# v8g.net
KiCad netlist of a schematic drawn in EAGLE
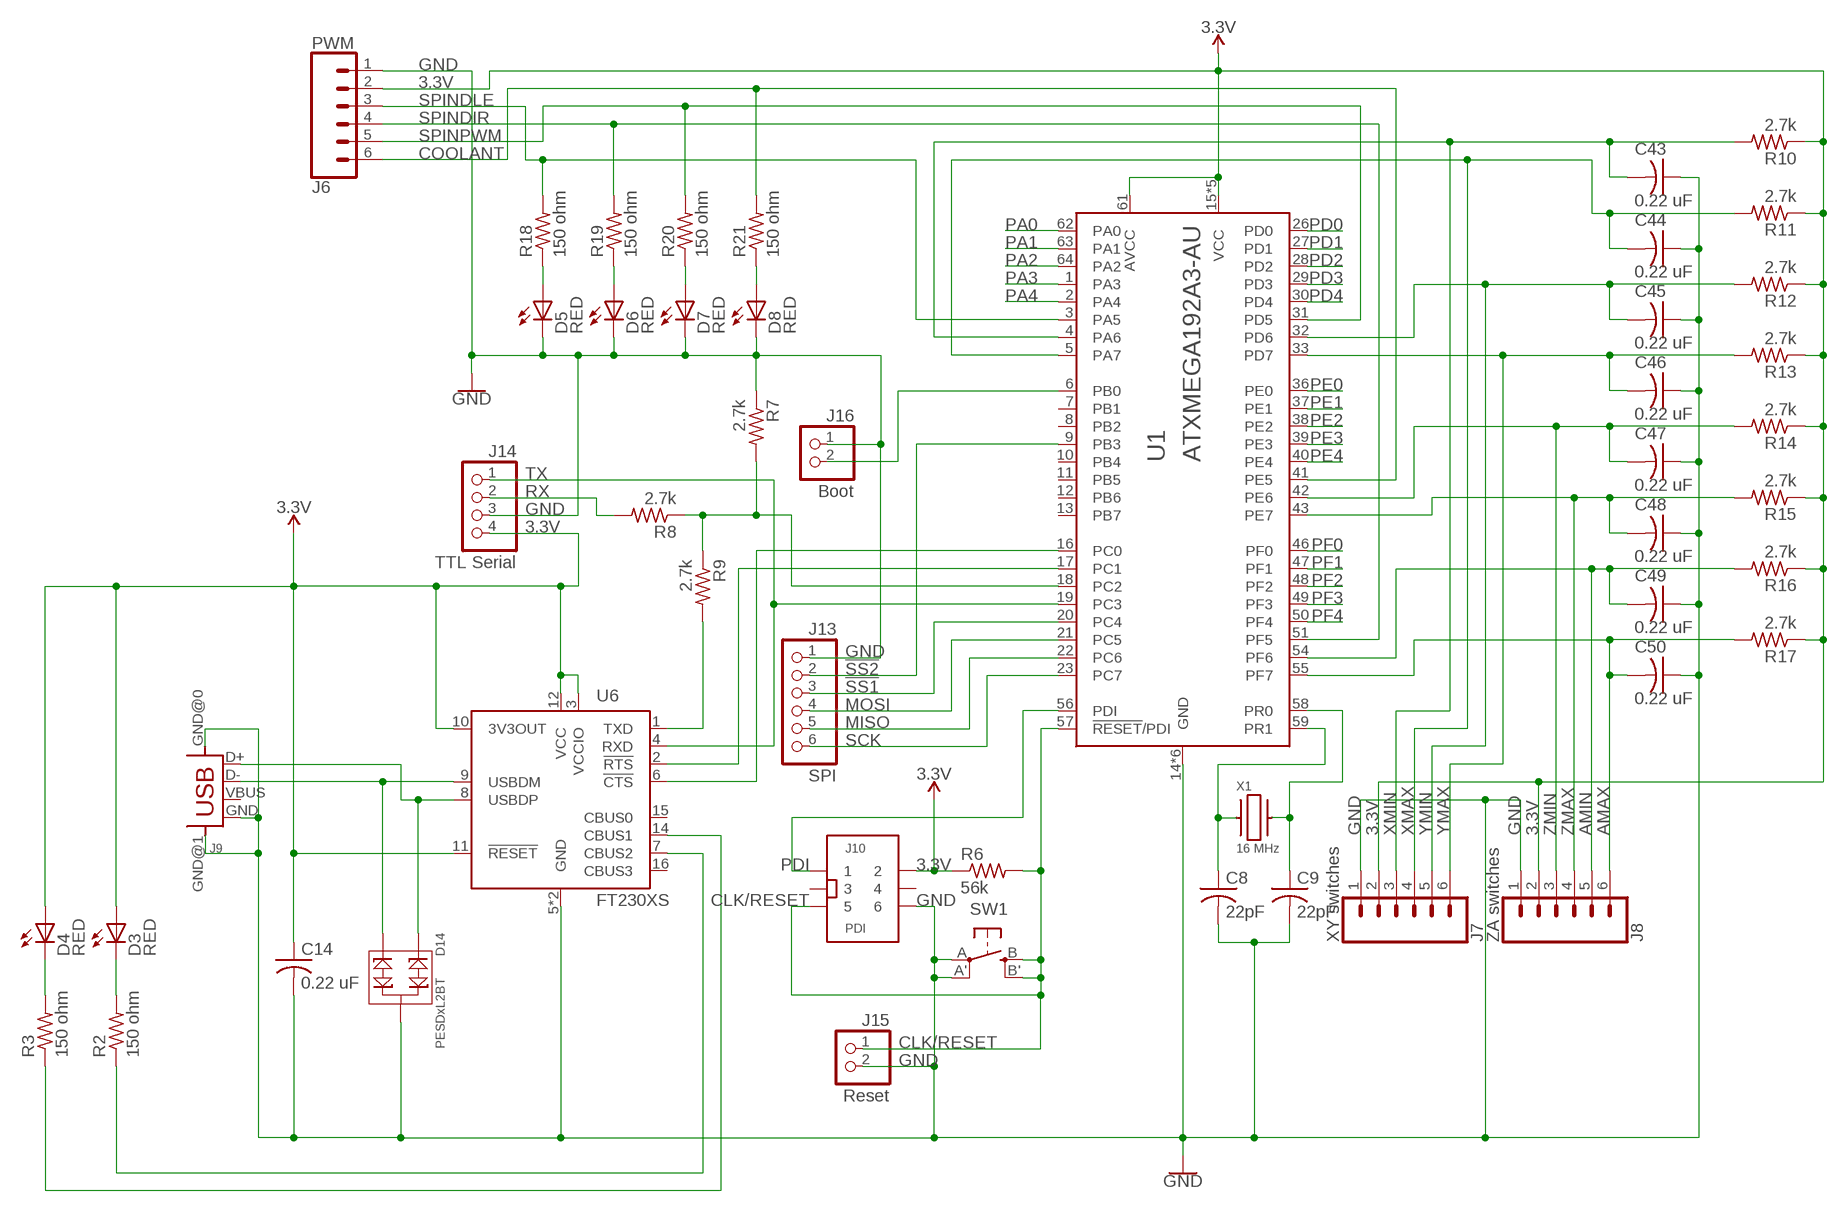
[diagram p0: schematic, sheet 1]
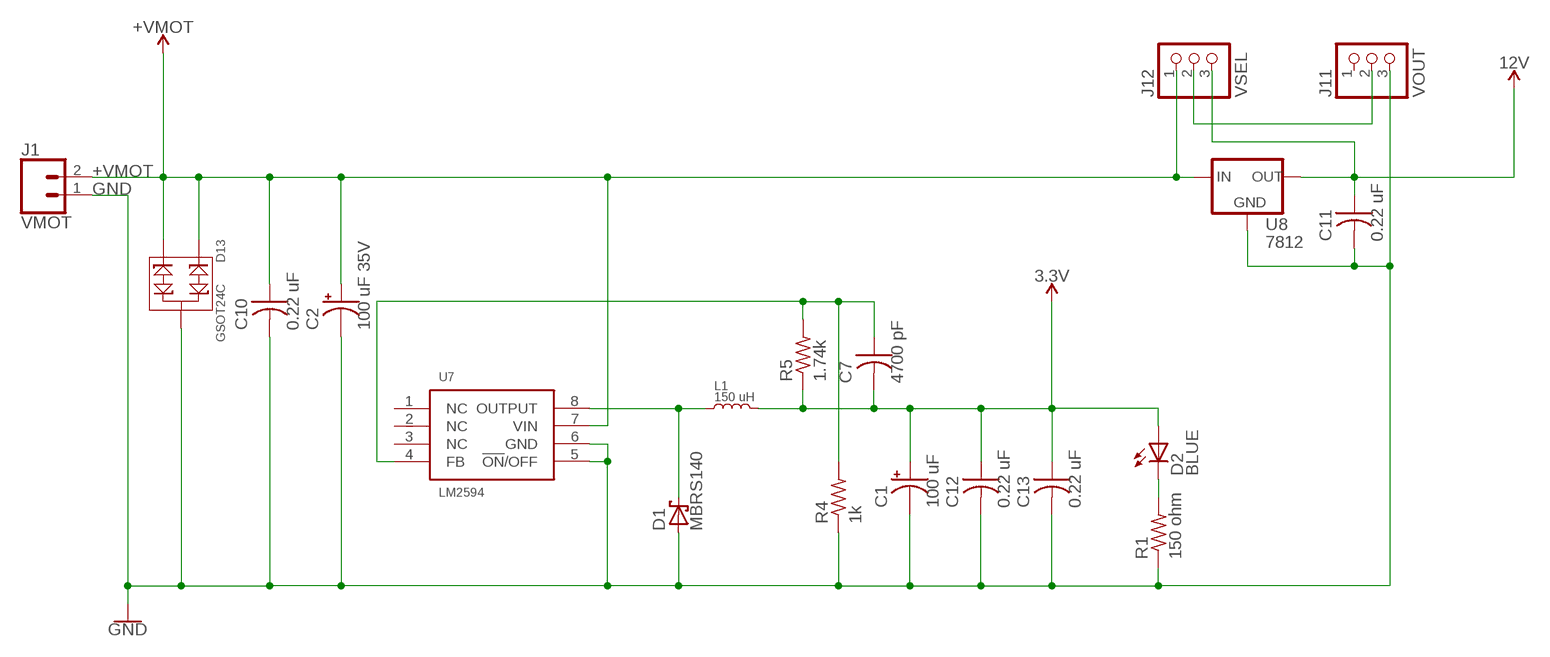
[diagram p1: schematic, sheet 2]
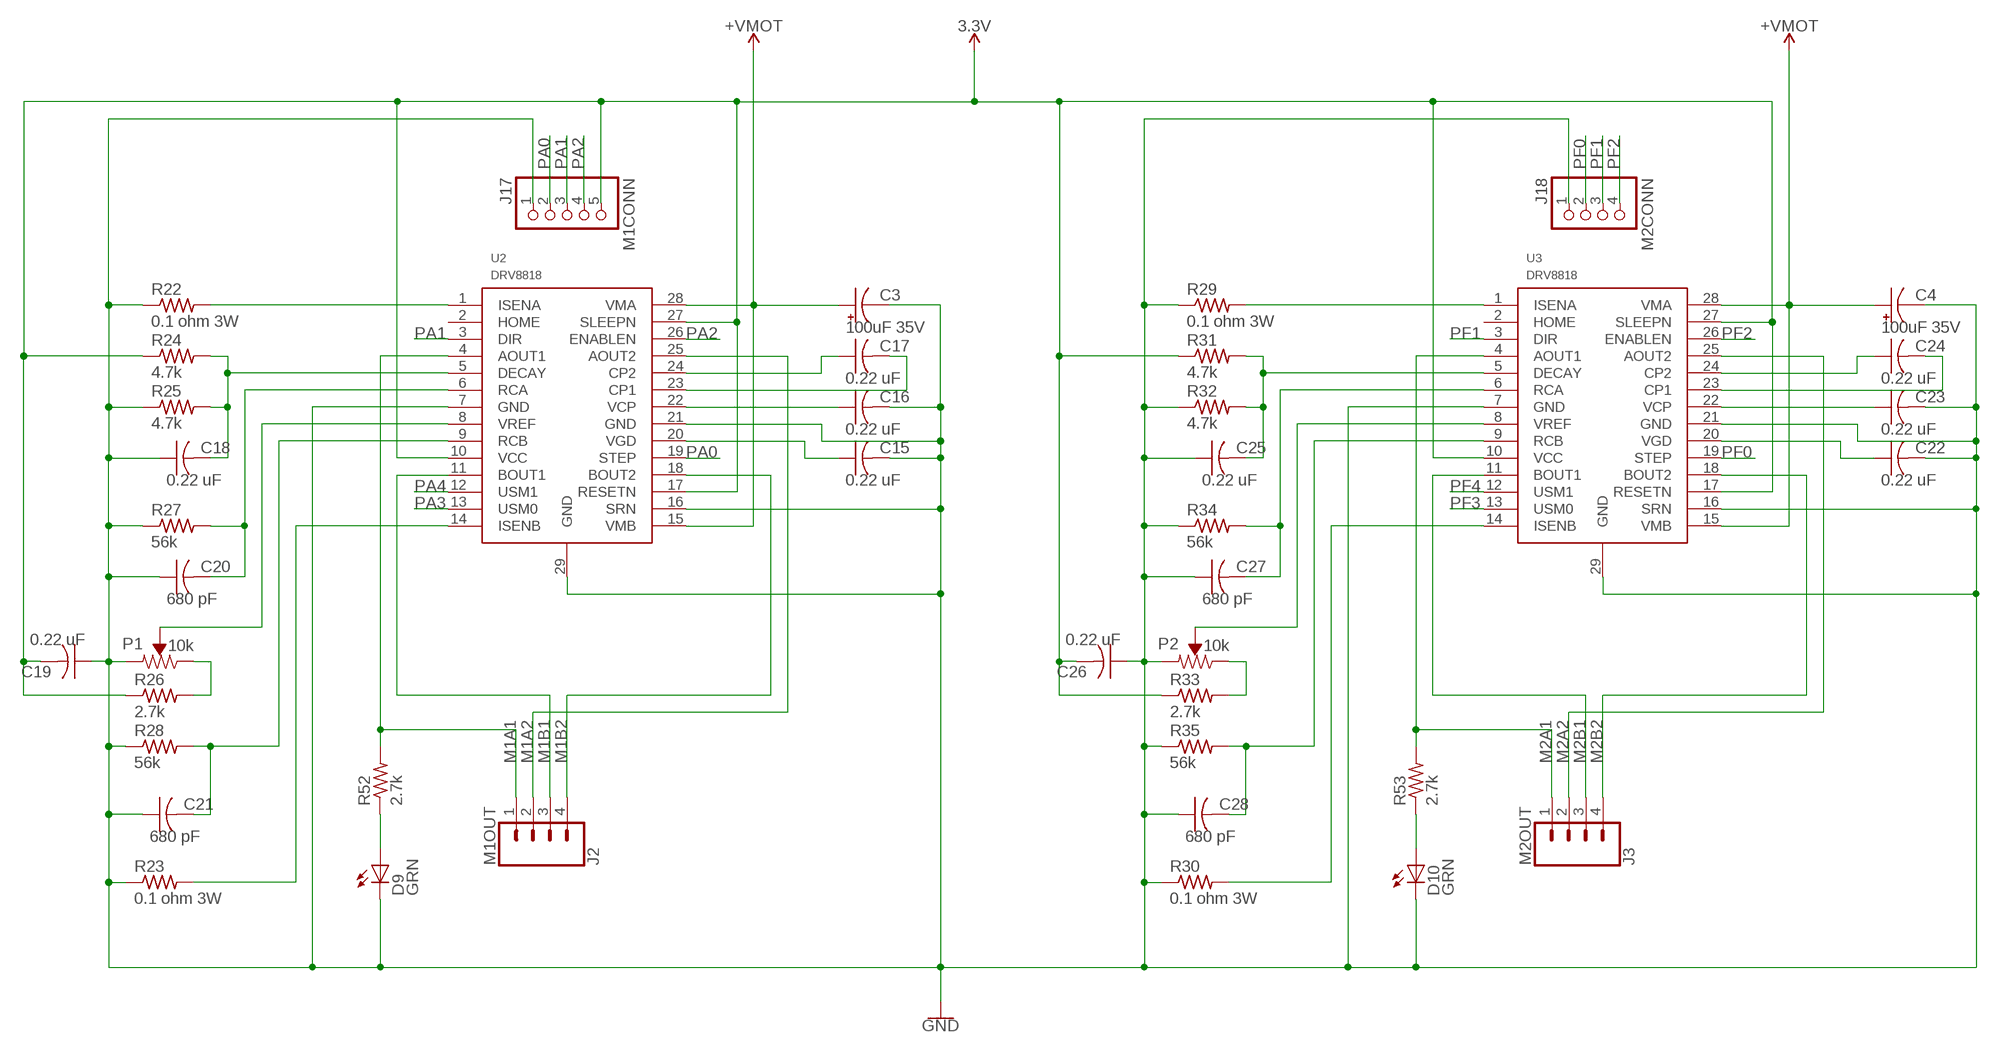
[diagram p2: schematic, sheet 3]
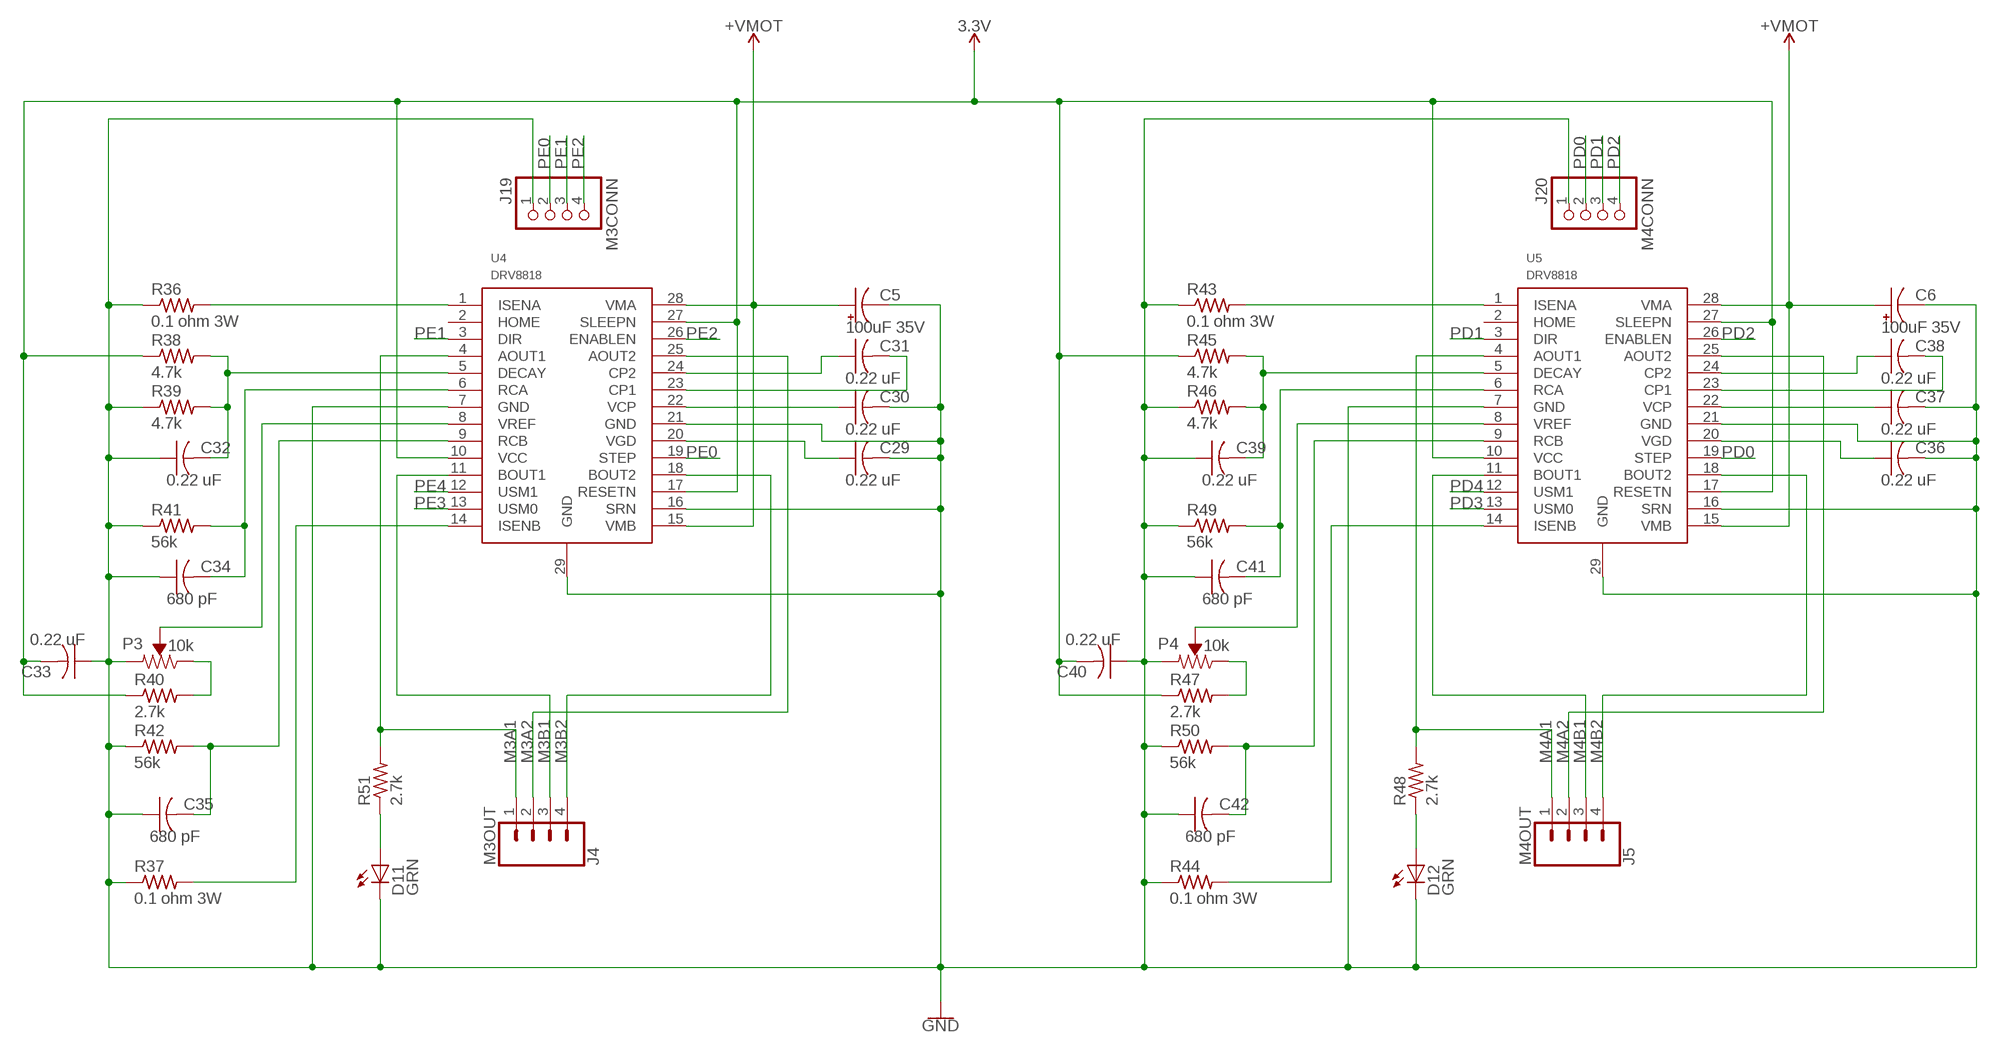
[diagram p3: schematic, sheet 4]

(export (version "E")
  (design (tool "Eeschema 10.0.6"))
  (components
    (comp (ref "C5")
      (value "100uF 35V")
      (footprint "eagle-import:WCAP-ASLI")
      (libsource (lib "eagle-import") (part "CPOL-US"))
    )
    (comp (ref "C6")
      (value "100uF 35V")
      (footprint "eagle-import:WCAP-ASLI")
      (libsource (lib "eagle-import") (part "CPOL-US"))
    )
    (comp (ref "C29")
      (value "0.22 uF")
      (footprint "eagle-import:C1206")
      (libsource (lib "eagle-import") (part "C-USC1206"))
    )
    (comp (ref "C30")
      (value "0.22 uF")
      (footprint "eagle-import:C1206")
      (libsource (lib "eagle-import") (part "C-USC1206"))
    )
    (comp (ref "C31")
      (value "0.22 uF")
      (footprint "eagle-import:C1206")
      (libsource (lib "eagle-import") (part "C-USC1206"))
    )
    (comp (ref "C32")
      (value "0.22 uF")
      (footprint "eagle-import:C1206")
      (libsource (lib "eagle-import") (part "C-USC1206"))
    )
    (comp (ref "C33")
      (value "0.22 uF")
      (footprint "eagle-import:C1206")
      (libsource (lib "eagle-import") (part "C-USC1206"))
    )
    (comp (ref "C34")
      (value "680 pF")
      (footprint "eagle-import:C1206")
      (libsource (lib "eagle-import") (part "C-USC1206"))
    )
    (comp (ref "C35")
      (value "680 pF")
      (footprint "eagle-import:C1206")
      (libsource (lib "eagle-import") (part "C-USC1206"))
    )
    (comp (ref "C36")
      (value "0.22 uF")
      (footprint "eagle-import:C1206")
      (libsource (lib "eagle-import") (part "C-USC1206"))
    )
    (comp (ref "C37")
      (value "0.22 uF")
      (footprint "eagle-import:C1206")
      (libsource (lib "eagle-import") (part "C-USC1206"))
    )
    (comp (ref "C38")
      (value "0.22 uF")
      (footprint "eagle-import:C1206")
      (libsource (lib "eagle-import") (part "C-USC1206"))
    )
    (comp (ref "C39")
      (value "0.22 uF")
      (footprint "eagle-import:C1206")
      (libsource (lib "eagle-import") (part "C-USC1206"))
    )
    (comp (ref "C40")
      (value "0.22 uF")
      (footprint "eagle-import:C1206")
      (libsource (lib "eagle-import") (part "C-USC1206"))
    )
    (comp (ref "C41")
      (value "680 pF")
      (footprint "eagle-import:C1206")
      (libsource (lib "eagle-import") (part "C-USC1206"))
    )
    (comp (ref "C42")
      (value "680 pF")
      (footprint "eagle-import:C1206")
      (libsource (lib "eagle-import") (part "C-USC1206"))
    )
    (comp (ref "D11")
      (value "GRN")
      (footprint "eagle-import:CHIPLED_1206")
      (libsource (lib "eagle-import") (part "LEDCHIPLED_1206"))
    )
    (comp (ref "D12")
      (value "GRN")
      (footprint "eagle-import:CHIPLED_1206")
      (libsource (lib "eagle-import") (part "LEDCHIPLED_1206"))
    )
    (comp (ref "J4")
      (value "M3OUT")
      (footprint "eagle-import:SCREWTERMINAL-3.5MM-4")
      (libsource (lib "eagle-import") (part "CONN_04SCREW"))
    )
    (comp (ref "J5")
      (value "M4OUT")
      (footprint "eagle-import:SCREWTERMINAL-3.5MM-4")
      (libsource (lib "eagle-import") (part "CONN_04SCREW"))
    )
    (comp (ref "J19")
      (value "M3CONN")
      (footprint "eagle-import:1X04")
      (libsource (lib "eagle-import") (part "PINHD-1X4"))
    )
    (comp (ref "J20")
      (value "M4CONN")
      (footprint "eagle-import:1X04")
      (libsource (lib "eagle-import") (part "PINHD-1X4"))
    )
    (comp (ref "P3")
      (value "10k")
      (footprint "eagle-import:BOURNS_3361P")
      (libsource (lib "eagle-import") (part "TRIMPOT"))
    )
    (comp (ref "P4")
      (value "10k")
      (footprint "eagle-import:BOURNS_3361P")
      (libsource (lib "eagle-import") (part "TRIMPOT"))
    )
    (comp (ref "R36")
      (value "0.1 ohm 3W")
      (footprint "eagle-import:R2512")
      (libsource (lib "eagle-import") (part "R-US_R2512"))
    )
    (comp (ref "R37")
      (value "0.1 ohm 3W")
      (footprint "eagle-import:R2512")
      (libsource (lib "eagle-import") (part "R-US_R2512"))
    )
    (comp (ref "R38")
      (value "4.7k")
      (footprint "eagle-import:R1206")
      (libsource (lib "eagle-import") (part "R-US_R1206"))
    )
    (comp (ref "R39")
      (value "4.7k")
      (footprint "eagle-import:R1206")
      (libsource (lib "eagle-import") (part "R-US_R1206"))
    )
    (comp (ref "R40")
      (value "2.7k")
      (footprint "eagle-import:R1206")
      (libsource (lib "eagle-import") (part "R-US_R1206"))
    )
    (comp (ref "R41")
      (value "56k")
      (footprint "eagle-import:R1206")
      (libsource (lib "eagle-import") (part "R-US_R1206"))
    )
    (comp (ref "R42")
      (value "56k")
      (footprint "eagle-import:R1206")
      (libsource (lib "eagle-import") (part "R-US_R1206"))
    )
    (comp (ref "R43")
      (value "0.1 ohm 3W")
      (footprint "eagle-import:R2512")
      (libsource (lib "eagle-import") (part "R-US_R2512"))
    )
    (comp (ref "R44")
      (value "0.1 ohm 3W")
      (footprint "eagle-import:R2512")
      (libsource (lib "eagle-import") (part "R-US_R2512"))
    )
    (comp (ref "R45")
      (value "4.7k")
      (footprint "eagle-import:R1206")
      (libsource (lib "eagle-import") (part "R-US_R1206"))
    )
    (comp (ref "R46")
      (value "4.7k")
      (footprint "eagle-import:R1206")
      (libsource (lib "eagle-import") (part "R-US_R1206"))
    )
    (comp (ref "R47")
      (value "2.7k")
      (footprint "eagle-import:R1206")
      (libsource (lib "eagle-import") (part "R-US_R1206"))
    )
    (comp (ref "R48")
      (value "2.7k")
      (footprint "eagle-import:0207_7")
      (libsource (lib "eagle-import") (part "R-US_0207/7"))
    )
    (comp (ref "R49")
      (value "56k")
      (footprint "eagle-import:R1206")
      (libsource (lib "eagle-import") (part "R-US_R1206"))
    )
    (comp (ref "R50")
      (value "56k")
      (footprint "eagle-import:R1206")
      (libsource (lib "eagle-import") (part "R-US_R1206"))
    )
    (comp (ref "R51")
      (value "2.7k")
      (footprint "eagle-import:0207_7")
      (libsource (lib "eagle-import") (part "R-US_0207/7"))
    )
    (comp (ref "U4")
      (value "DRV8818")
      (footprint "eagle-import:HTSSOP_28-PIN")
      (libsource (lib "eagle-import") (part "DRV8818"))
    )
    (comp (ref "U5")
      (value "DRV8818")
      (footprint "eagle-import:HTSSOP_28-PIN")
      (libsource (lib "eagle-import") (part "DRV8818"))
    )
    (comp (ref "C3")
      (value "100uF 35V")
      (footprint "eagle-import:WCAP-ASLI")
      (libsource (lib "eagle-import") (part "CPOL-US"))
    )
    (comp (ref "C4")
      (value "100uF 35V")
      (footprint "eagle-import:WCAP-ASLI")
      (libsource (lib "eagle-import") (part "CPOL-US"))
    )
    (comp (ref "C15")
      (value "0.22 uF")
      (footprint "eagle-import:C1206")
      (libsource (lib "eagle-import") (part "C-USC1206"))
    )
    (comp (ref "C16")
      (value "0.22 uF")
      (footprint "eagle-import:C1206")
      (libsource (lib "eagle-import") (part "C-USC1206"))
    )
    (comp (ref "C17")
      (value "0.22 uF")
      (footprint "eagle-import:C1206")
      (libsource (lib "eagle-import") (part "C-USC1206"))
    )
    (comp (ref "C18")
      (value "0.22 uF")
      (footprint "eagle-import:C1206")
      (libsource (lib "eagle-import") (part "C-USC1206"))
    )
    (comp (ref "C19")
      (value "0.22 uF")
      (footprint "eagle-import:C1206")
      (libsource (lib "eagle-import") (part "C-USC1206"))
    )
    (comp (ref "C20")
      (value "680 pF")
      (footprint "eagle-import:C1206")
      (libsource (lib "eagle-import") (part "C-USC1206"))
    )
    (comp (ref "C21")
      (value "680 pF")
      (footprint "eagle-import:C1206")
      (libsource (lib "eagle-import") (part "C-USC1206"))
    )
    (comp (ref "C22")
      (value "0.22 uF")
      (footprint "eagle-import:C1206")
      (libsource (lib "eagle-import") (part "C-USC1206"))
    )
    (comp (ref "C23")
      (value "0.22 uF")
      (footprint "eagle-import:C1206")
      (libsource (lib "eagle-import") (part "C-USC1206"))
    )
    (comp (ref "C24")
      (value "0.22 uF")
      (footprint "eagle-import:C1206")
      (libsource (lib "eagle-import") (part "C-USC1206"))
    )
    (comp (ref "C25")
      (value "0.22 uF")
      (footprint "eagle-import:C1206")
      (libsource (lib "eagle-import") (part "C-USC1206"))
    )
    (comp (ref "C26")
      (value "0.22 uF")
      (footprint "eagle-import:C1206")
      (libsource (lib "eagle-import") (part "C-USC1206"))
    )
    (comp (ref "C27")
      (value "680 pF")
      (footprint "eagle-import:C1206")
      (libsource (lib "eagle-import") (part "C-USC1206"))
    )
    (comp (ref "C28")
      (value "680 pF")
      (footprint "eagle-import:C1206")
      (libsource (lib "eagle-import") (part "C-USC1206"))
    )
    (comp (ref "D9")
      (value "GRN")
      (footprint "eagle-import:CHIPLED_1206")
      (libsource (lib "eagle-import") (part "LEDCHIPLED_1206"))
    )
    (comp (ref "D10")
      (value "GRN")
      (footprint "eagle-import:CHIPLED_1206")
      (libsource (lib "eagle-import") (part "LEDCHIPLED_1206"))
    )
    (comp (ref "J2")
      (value "M1OUT")
      (footprint "eagle-import:SCREWTERMINAL-3.5MM-4")
      (libsource (lib "eagle-import") (part "CONN_04SCREW"))
    )
    (comp (ref "J3")
      (value "M2OUT")
      (footprint "eagle-import:SCREWTERMINAL-3.5MM-4")
      (libsource (lib "eagle-import") (part "CONN_04SCREW"))
    )
    (comp (ref "J17")
      (value "M1CONN")
      (footprint "eagle-import:1X05")
      (libsource (lib "eagle-import") (part "PINHD-1X5"))
    )
    (comp (ref "J18")
      (value "M2CONN")
      (footprint "eagle-import:1X04")
      (libsource (lib "eagle-import") (part "PINHD-1X4"))
    )
    (comp (ref "P1")
      (value "10k")
      (footprint "eagle-import:BOURNS_3361P")
      (libsource (lib "eagle-import") (part "TRIMPOT"))
    )
    (comp (ref "P2")
      (value "10k")
      (footprint "eagle-import:BOURNS_3361P")
      (libsource (lib "eagle-import") (part "TRIMPOT"))
    )
    (comp (ref "R22")
      (value "0.1 ohm 3W")
      (footprint "eagle-import:R2512")
      (libsource (lib "eagle-import") (part "R-US_R2512"))
    )
    (comp (ref "R23")
      (value "0.1 ohm 3W")
      (footprint "eagle-import:R2512")
      (libsource (lib "eagle-import") (part "R-US_R2512"))
    )
    (comp (ref "R24")
      (value "4.7k")
      (footprint "eagle-import:R1206")
      (libsource (lib "eagle-import") (part "R-US_R1206"))
    )
    (comp (ref "R25")
      (value "4.7k")
      (footprint "eagle-import:R1206")
      (libsource (lib "eagle-import") (part "R-US_R1206"))
    )
    (comp (ref "R26")
      (value "2.7k")
      (footprint "eagle-import:R1206")
      (libsource (lib "eagle-import") (part "R-US_R1206"))
    )
    (comp (ref "R27")
      (value "56k")
      (footprint "eagle-import:R1206")
      (libsource (lib "eagle-import") (part "R-US_R1206"))
    )
    (comp (ref "R28")
      (value "56k")
      (footprint "eagle-import:R1206")
      (libsource (lib "eagle-import") (part "R-US_R1206"))
    )
    (comp (ref "R29")
      (value "0.1 ohm 3W")
      (footprint "eagle-import:R2512")
      (libsource (lib "eagle-import") (part "R-US_R2512"))
    )
    (comp (ref "R30")
      (value "0.1 ohm 3W")
      (footprint "eagle-import:R2512")
      (libsource (lib "eagle-import") (part "R-US_R2512"))
    )
    (comp (ref "R31")
      (value "4.7k")
      (footprint "eagle-import:R1206")
      (libsource (lib "eagle-import") (part "R-US_R1206"))
    )
    (comp (ref "R32")
      (value "4.7k")
      (footprint "eagle-import:R1206")
      (libsource (lib "eagle-import") (part "R-US_R1206"))
    )
    (comp (ref "R33")
      (value "2.7k")
      (footprint "eagle-import:R1206")
      (libsource (lib "eagle-import") (part "R-US_R1206"))
    )
    (comp (ref "R34")
      (value "56k")
      (footprint "eagle-import:R1206")
      (libsource (lib "eagle-import") (part "R-US_R1206"))
    )
    (comp (ref "R35")
      (value "56k")
      (footprint "eagle-import:R1206")
      (libsource (lib "eagle-import") (part "R-US_R1206"))
    )
    (comp (ref "R52")
      (value "2.7k")
      (footprint "eagle-import:0207_7")
      (libsource (lib "eagle-import") (part "R-US_0207/7"))
    )
    (comp (ref "R53")
      (value "2.7k")
      (footprint "eagle-import:0207_7")
      (libsource (lib "eagle-import") (part "R-US_0207/7"))
    )
    (comp (ref "U2")
      (value "DRV8818")
      (footprint "eagle-import:HTSSOP_28-PIN")
      (libsource (lib "eagle-import") (part "DRV8818"))
    )
    (comp (ref "U3")
      (value "DRV8818")
      (footprint "eagle-import:HTSSOP_28-PIN")
      (libsource (lib "eagle-import") (part "DRV8818"))
    )
    (comp (ref "C8")
      (value "22pF")
      (footprint "eagle-import:C1206")
      (libsource (lib "eagle-import") (part "C-USC1206"))
    )
    (comp (ref "C9")
      (value "22pF")
      (footprint "eagle-import:C1206")
      (libsource (lib "eagle-import") (part "C-USC1206"))
    )
    (comp (ref "C14")
      (value "0.22 uF")
      (footprint "eagle-import:C1206")
      (libsource (lib "eagle-import") (part "C-USC1206"))
    )
    (comp (ref "C43")
      (value "0.22 uF")
      (footprint "eagle-import:C1206")
      (libsource (lib "eagle-import") (part "C-USC1206"))
    )
    (comp (ref "C44")
      (value "0.22 uF")
      (footprint "eagle-import:C1206")
      (libsource (lib "eagle-import") (part "C-USC1206"))
    )
    (comp (ref "C45")
      (value "0.22 uF")
      (footprint "eagle-import:C1206")
      (libsource (lib "eagle-import") (part "C-USC1206"))
    )
    (comp (ref "C46")
      (value "0.22 uF")
      (footprint "eagle-import:C1206")
      (libsource (lib "eagle-import") (part "C-USC1206"))
    )
    (comp (ref "C47")
      (value "0.22 uF")
      (footprint "eagle-import:C1206")
      (libsource (lib "eagle-import") (part "C-USC1206"))
    )
    (comp (ref "C48")
      (value "0.22 uF")
      (footprint "eagle-import:C1206")
      (libsource (lib "eagle-import") (part "C-USC1206"))
    )
    (comp (ref "C49")
      (value "0.22 uF")
      (footprint "eagle-import:C1206")
      (libsource (lib "eagle-import") (part "C-USC1206"))
    )
    (comp (ref "C50")
      (value "0.22 uF")
      (footprint "eagle-import:C1206")
      (libsource (lib "eagle-import") (part "C-USC1206"))
    )
    (comp (ref "D3")
      (value "RED")
      (footprint "eagle-import:CHIPLED_1206")
      (libsource (lib "eagle-import") (part "LEDCHIPLED_1206"))
    )
    (comp (ref "D4")
      (value "RED")
      (footprint "eagle-import:CHIPLED_1206")
      (libsource (lib "eagle-import") (part "LEDCHIPLED_1206"))
    )
    (comp (ref "D5")
      (value "RED")
      (footprint "eagle-import:CHIPLED_1206")
      (libsource (lib "eagle-import") (part "LEDCHIPLED_1206"))
    )
    (comp (ref "D6")
      (value "RED")
      (footprint "eagle-import:CHIPLED_1206")
      (libsource (lib "eagle-import") (part "LEDCHIPLED_1206"))
    )
    (comp (ref "D7")
      (value "RED")
      (footprint "eagle-import:CHIPLED_1206")
      (libsource (lib "eagle-import") (part "LEDCHIPLED_1206"))
    )
    (comp (ref "D8")
      (value "RED")
      (footprint "eagle-import:CHIPLED_1206")
      (libsource (lib "eagle-import") (part "LEDCHIPLED_1206"))
    )
    (comp (ref "D14")
      (value "PESDxL2BT")
      (footprint "eagle-import:SOT23")
      (libsource (lib "eagle-import") (part "D-ESD-PESDXL2BT"))
    )
    (comp (ref "J6")
      (value "PWM")
      (footprint "eagle-import:SCREWTERMINAL-3.5MM-6")
      (libsource (lib "eagle-import") (part "CONN_063.5MM-6"))
    )
    (comp (ref "J7")
      (value "XY switches")
      (footprint "eagle-import:SCREWTERMINAL-3.5MM-6")
      (libsource (lib "eagle-import") (part "CONN_063.5MM-6"))
    )
    (comp (ref "J8")
      (value "ZA switches")
      (footprint "eagle-import:SCREWTERMINAL-3.5MM-6")
      (libsource (lib "eagle-import") (part "CONN_063.5MM-6"))
    )
    (comp (ref "J9")
      (value "USB")
      (footprint "eagle-import:USB-B-H")
      (libsource (lib "eagle-import") (part "USB-B-H"))
    )
    (comp (ref "J10")
      (value "PDI")
      (footprint "eagle-import:IDC-6-PIN-61200621621")
      (libsource (lib "eagle-import") (part "IDC-6-PIN-61200621621"))
    )
    (comp (ref "J13")
      (value "SPI")
      (footprint "eagle-import:1X06")
      (libsource (lib "eagle-import") (part "PINHD-1X6"))
    )
    (comp (ref "J14")
      (value "TTL Serial")
      (footprint "eagle-import:1X04")
      (libsource (lib "eagle-import") (part "PINHD-1X4"))
    )
    (comp (ref "J15")
      (value "Reset")
      (footprint "eagle-import:1X02")
      (libsource (lib "eagle-import") (part "PINHD-1X2"))
    )
    (comp (ref "J16")
      (value "Boot")
      (footprint "eagle-import:1X02")
      (libsource (lib "eagle-import") (part "PINHD-1X2"))
    )
    (comp (ref "R2")
      (value "150 ohm")
      (footprint "eagle-import:M1206")
      (libsource (lib "eagle-import") (part "R-US_M1206"))
    )
    (comp (ref "R3")
      (value "150 ohm")
      (footprint "eagle-import:M1206")
      (libsource (lib "eagle-import") (part "R-US_M1206"))
    )
    (comp (ref "R6")
      (value "56k")
      (footprint "eagle-import:M1206")
      (libsource (lib "eagle-import") (part "R-US_M1206"))
    )
    (comp (ref "R7")
      (value "2.7k")
      (footprint "eagle-import:M1206")
      (libsource (lib "eagle-import") (part "R-US_M1206"))
    )
    (comp (ref "R8")
      (value "2.7k")
      (footprint "eagle-import:M1206")
      (libsource (lib "eagle-import") (part "R-US_M1206"))
    )
    (comp (ref "R9")
      (value "2.7k")
      (footprint "eagle-import:M1206")
      (libsource (lib "eagle-import") (part "R-US_M1206"))
    )
    (comp (ref "R10")
      (value "2.7k")
      (footprint "eagle-import:M1206")
      (libsource (lib "eagle-import") (part "R-US_M1206"))
    )
    (comp (ref "R11")
      (value "2.7k")
      (footprint "eagle-import:M1206")
      (libsource (lib "eagle-import") (part "R-US_M1206"))
    )
    (comp (ref "R12")
      (value "2.7k")
      (footprint "eagle-import:M1206")
      (libsource (lib "eagle-import") (part "R-US_M1206"))
    )
    (comp (ref "R13")
      (value "2.7k")
      (footprint "eagle-import:M1206")
      (libsource (lib "eagle-import") (part "R-US_M1206"))
    )
    (comp (ref "R14")
      (value "2.7k")
      (footprint "eagle-import:M1206")
      (libsource (lib "eagle-import") (part "R-US_M1206"))
    )
    (comp (ref "R15")
      (value "2.7k")
      (footprint "eagle-import:M1206")
      (libsource (lib "eagle-import") (part "R-US_M1206"))
    )
    (comp (ref "R16")
      (value "2.7k")
      (footprint "eagle-import:M1206")
      (libsource (lib "eagle-import") (part "R-US_M1206"))
    )
    (comp (ref "R17")
      (value "2.7k")
      (footprint "eagle-import:M1206")
      (libsource (lib "eagle-import") (part "R-US_M1206"))
    )
    (comp (ref "R18")
      (value "150 ohm")
      (footprint "eagle-import:M1206")
      (libsource (lib "eagle-import") (part "R-US_M1206"))
    )
    (comp (ref "R19")
      (value "150 ohm")
      (footprint "eagle-import:M1206")
      (libsource (lib "eagle-import") (part "R-US_M1206"))
    )
    (comp (ref "R20")
      (value "150 ohm")
      (footprint "eagle-import:M1206")
      (libsource (lib "eagle-import") (part "R-US_M1206"))
    )
    (comp (ref "R21")
      (value "150 ohm")
      (footprint "eagle-import:M1206")
      (libsource (lib "eagle-import") (part "R-US_M1206"))
    )
    (comp (ref "SW1")
      (value "SPST_TACT-EVQQ2")
      (footprint "eagle-import:EVQ-Q2")
      (libsource (lib "eagle-import") (part "SPST_TACT-EVQQ2"))
    )
    (comp (ref "U1")
      (value "ATXMEGA192A3-AU")
      (footprint "eagle-import:TQFP-64A-64")
      (libsource (lib "eagle-import") (part "ATXMEGA192A3-AU"))
    )
    (comp (ref "U6")
      (value "FT230XS")
      (footprint "eagle-import:SSOP16")
      (fields (field (name "MF") "FTDI"))
      (libsource (lib "eagle-import") (part "FT230XS"))
    )
    (comp (ref "X1")
      (value "16 MHz")
      (footprint "eagle-import:C4ST-SMD")
      (libsource (lib "eagle-import") (part "C4STSMD"))
    )
    (comp (ref "C1")
      (value "100 uF")
      (footprint "eagle-import:WCAP-ASLI")
      (libsource (lib "eagle-import") (part "CPOL-US"))
    )
    (comp (ref "C2")
      (value "100 uF 35V")
      (footprint "eagle-import:WCAP-ASLI")
      (libsource (lib "eagle-import") (part "CPOL-US"))
    )
    (comp (ref "C7")
      (value "4700 pF")
      (footprint "eagle-import:C1206")
      (libsource (lib "eagle-import") (part "C-USC1206"))
    )
    (comp (ref "C10")
      (value "0.22 uF")
      (footprint "eagle-import:C1206")
      (libsource (lib "eagle-import") (part "C-USC1206"))
    )
    (comp (ref "C11")
      (value "0.22 uF")
      (footprint "eagle-import:C1206")
      (libsource (lib "eagle-import") (part "C-USC1206"))
    )
    (comp (ref "C12")
      (value "0.22 uF")
      (footprint "eagle-import:C1206")
      (libsource (lib "eagle-import") (part "C-USC1206"))
    )
    (comp (ref "C13")
      (value "0.22 uF")
      (footprint "eagle-import:C1206")
      (libsource (lib "eagle-import") (part "C-USC1206"))
    )
    (comp (ref "D1")
      (value "MBRS140")
      (footprint "eagle-import:DO-214AA")
      (libsource (lib "eagle-import") (part "SHOTTKY-DIODESMBRS140"))
    )
    (comp (ref "D2")
      (value "BLUE")
      (footprint "eagle-import:CHIPLED_1206")
      (libsource (lib "eagle-import") (part "LEDCHIPLED_1206"))
    )
    (comp (ref "D13")
      (value "GSOT24C")
      (footprint "eagle-import:SOT23")
      (libsource (lib "eagle-import") (part "D-ESD-PESDXL2BT"))
    )
    (comp (ref "J1")
      (value "VMOT")
      (footprint "eagle-import:SCREWTERMINAL-5MM-2")
      (libsource (lib "eagle-import") (part "CONN_025MM"))
    )
    (comp (ref "J11")
      (value "VOUT")
      (footprint "eagle-import:1X03")
      (libsource (lib "eagle-import") (part "PINHD-1X3"))
    )
    (comp (ref "J12")
      (value "VSEL")
      (footprint "eagle-import:1X03")
      (libsource (lib "eagle-import") (part "PINHD-1X3"))
    )
    (comp (ref "L1")
      (value "150 uH")
      (footprint "eagle-import:SDE0805A")
      (libsource (lib "eagle-import") (part "SDE0805A-471K"))
    )
    (comp (ref "R1")
      (value "150 ohm")
      (footprint "eagle-import:R1206")
      (libsource (lib "eagle-import") (part "R-US_R1206"))
    )
    (comp (ref "R4")
      (value "1k")
      (footprint "eagle-import:R1206")
      (libsource (lib "eagle-import") (part "R-US_R1206"))
    )
    (comp (ref "R5")
      (value "1.74k")
      (footprint "eagle-import:R1206")
      (libsource (lib "eagle-import") (part "R-US_R1206"))
    )
    (comp (ref "U7")
      (value "LM2594")
      (footprint "eagle-import:SOIC-8_NB")
      (libsource (lib "eagle-import") (part "LM2594"))
    )
    (comp (ref "U8")
      (value "7812")
      (footprint "eagle-import:D2PAK")
      (libsource (lib "eagle-import") (part "L78XXD2TT"))
    )
  )
  (nets
    (net (code "1") (name "+VMOT") (class "Default")
      (node (ref "C10") (pin "1") (pinfunction "1_1") (pintype "passive"))
      (node (ref "C2") (pin "+") (pinfunction "+_+") (pintype "passive"))
      (node (ref "C3") (pin "+") (pinfunction "+_+") (pintype "passive"))
      (node (ref "C4") (pin "+") (pinfunction "+_+") (pintype "passive"))
      (node (ref "C5") (pin "+") (pinfunction "+_+") (pintype "passive"))
      (node (ref "C6") (pin "+") (pinfunction "+_+") (pintype "passive"))
      (node (ref "D13") (pin "1") (pinfunction "1_1") (pintype "power_in"))
      (node (ref "D13") (pin "2") (pinfunction "2_2") (pintype "power_in"))
      (node (ref "J1") (pin "2") (pinfunction "2_2") (pintype "passive"))
      (node (ref "J12") (pin "1") (pinfunction "1_1") (pintype "passive"))
      (node (ref "U2") (pin "15") (pinfunction "VMB_15") (pintype "bidirectional"))
      (node (ref "U2") (pin "28") (pinfunction "VMA_28") (pintype "bidirectional"))
      (node (ref "U3") (pin "15") (pinfunction "VMB_15") (pintype "bidirectional"))
      (node (ref "U3") (pin "28") (pinfunction "VMA_28") (pintype "bidirectional"))
      (node (ref "U4") (pin "15") (pinfunction "VMB_15") (pintype "bidirectional"))
      (node (ref "U4") (pin "28") (pinfunction "VMA_28") (pintype "bidirectional"))
      (node (ref "U5") (pin "15") (pinfunction "VMB_15") (pintype "bidirectional"))
      (node (ref "U5") (pin "28") (pinfunction "VMA_28") (pintype "bidirectional"))
      (node (ref "U7") (pin "7") (pinfunction "VIN_7") (pintype "bidirectional"))
      (node (ref "U8") (pin "1") (pinfunction "IN_1") (pintype "input"))
    )
    (net (code "2") (name "3.3V") (class "Default")
      (node (ref "C1") (pin "+") (pinfunction "+_+") (pintype "passive"))
      (node (ref "C12") (pin "1") (pinfunction "1_1") (pintype "passive"))
      (node (ref "C13") (pin "1") (pinfunction "1_1") (pintype "passive"))
      (node (ref "C14") (pin "1") (pinfunction "1_1") (pintype "passive"))
      (node (ref "C19") (pin "2") (pinfunction "2_2") (pintype "passive"))
      (node (ref "C26") (pin "2") (pinfunction "2_2") (pintype "passive"))
      (node (ref "C33") (pin "2") (pinfunction "2_2") (pintype "passive"))
      (node (ref "C40") (pin "2") (pinfunction "2_2") (pintype "passive"))
      (node (ref "C7") (pin "2") (pinfunction "2_2") (pintype "passive"))
      (node (ref "D2") (pin "A") (pinfunction "A_A") (pintype "passive"))
      (node (ref "D3") (pin "A") (pinfunction "A_A") (pintype "passive"))
      (node (ref "D4") (pin "A") (pinfunction "A_A") (pintype "passive"))
      (node (ref "J10") (pin "2") (pinfunction "2_2") (pintype "bidirectional"))
      (node (ref "J14") (pin "4") (pinfunction "4_4") (pintype "passive"))
      (node (ref "J17") (pin "5") (pinfunction "5_5") (pintype "passive"))
      (node (ref "J6") (pin "2") (pinfunction "2_2") (pintype "passive"))
      (node (ref "J7") (pin "2") (pinfunction "2_2") (pintype "passive"))
      (node (ref "J8") (pin "2") (pinfunction "2_2") (pintype "passive"))
      (node (ref "L1") (pin "2") (pinfunction "2_2") (pintype "bidirectional"))
      (node (ref "R10") (pin "1") (pinfunction "1_1") (pintype "passive"))
      (node (ref "R11") (pin "1") (pinfunction "1_1") (pintype "passive"))
      (node (ref "R12") (pin "1") (pinfunction "1_1") (pintype "passive"))
      (node (ref "R13") (pin "1") (pinfunction "1_1") (pintype "passive"))
      (node (ref "R14") (pin "1") (pinfunction "1_1") (pintype "passive"))
      (node (ref "R15") (pin "1") (pinfunction "1_1") (pintype "passive"))
      (node (ref "R16") (pin "1") (pinfunction "1_1") (pintype "passive"))
      (node (ref "R17") (pin "1") (pinfunction "1_1") (pintype "passive"))
      (node (ref "R24") (pin "1") (pinfunction "1_1") (pintype "passive"))
      (node (ref "R26") (pin "1") (pinfunction "1_1") (pintype "passive"))
      (node (ref "R31") (pin "1") (pinfunction "1_1") (pintype "passive"))
      (node (ref "R33") (pin "1") (pinfunction "1_1") (pintype "passive"))
      (node (ref "R38") (pin "1") (pinfunction "1_1") (pintype "passive"))
      (node (ref "R40") (pin "1") (pinfunction "1_1") (pintype "passive"))
      (node (ref "R45") (pin "1") (pinfunction "1_1") (pintype "passive"))
      (node (ref "R47") (pin "1") (pinfunction "1_1") (pintype "passive"))
      (node (ref "R5") (pin "1") (pinfunction "1_1") (pintype "passive"))
      (node (ref "R6") (pin "1") (pinfunction "1_1") (pintype "passive"))
      (node (ref "U1") (pin "15") (pinfunction "VCC_15") (pintype "power_in"))
      (node (ref "U1") (pin "25") (pinfunction "VCC_25") (pintype "power_in"))
      (node (ref "U1") (pin "35") (pinfunction "VCC_35") (pintype "power_in"))
      (node (ref "U1") (pin "45") (pinfunction "VCC_45") (pintype "power_in"))
      (node (ref "U1") (pin "53") (pinfunction "VCC_53") (pintype "power_in"))
      (node (ref "U1") (pin "61") (pinfunction "AVCC_61") (pintype "power_in"))
      (node (ref "U2") (pin "10") (pinfunction "VCC_10") (pintype "bidirectional"))
      (node (ref "U2") (pin "17") (pinfunction "RESETN_17") (pintype "bidirectional"))
      (node (ref "U2") (pin "27") (pinfunction "SLEEPN_27") (pintype "bidirectional"))
      (node (ref "U3") (pin "10") (pinfunction "VCC_10") (pintype "bidirectional"))
      (node (ref "U3") (pin "17") (pinfunction "RESETN_17") (pintype "bidirectional"))
      (node (ref "U3") (pin "27") (pinfunction "SLEEPN_27") (pintype "bidirectional"))
      (node (ref "U4") (pin "10") (pinfunction "VCC_10") (pintype "bidirectional"))
      (node (ref "U4") (pin "17") (pinfunction "RESETN_17") (pintype "bidirectional"))
      (node (ref "U4") (pin "27") (pinfunction "SLEEPN_27") (pintype "bidirectional"))
      (node (ref "U5") (pin "10") (pinfunction "VCC_10") (pintype "bidirectional"))
      (node (ref "U5") (pin "17") (pinfunction "RESETN_17") (pintype "bidirectional"))
      (node (ref "U5") (pin "27") (pinfunction "SLEEPN_27") (pintype "bidirectional"))
      (node (ref "U6") (pin "10") (pinfunction "3V3OUT_10") (pintype "passive"))
      (node (ref "U6") (pin "11") (pinfunction "~{RESET}_11") (pintype "input"))
      (node (ref "U6") (pin "12") (pinfunction "VCC_12") (pintype "power_in"))
      (node (ref "U6") (pin "3") (pinfunction "VCCIO_3") (pintype "power_in"))
    )
    (net (code "3") (name "12V") (class "Default")
      (node (ref "C11") (pin "1") (pinfunction "1_1") (pintype "passive"))
      (node (ref "J12") (pin "3") (pinfunction "3_3") (pintype "passive"))
      (node (ref "U8") (pin "3") (pinfunction "OUT_3") (pintype "passive"))
    )
    (net (code "4") (name "AMAX") (class "Default")
      (node (ref "C50") (pin "2") (pinfunction "2_2") (pintype "passive"))
      (node (ref "J8") (pin "6") (pinfunction "6_6") (pintype "passive"))
      (node (ref "R17") (pin "2") (pinfunction "2_2") (pintype "passive"))
      (node (ref "U1") (pin "55") (pinfunction "PF7_55") (pintype "bidirectional"))
    )
    (net (code "5") (name "AMIN") (class "Default")
      (node (ref "C49") (pin "2") (pinfunction "2_2") (pintype "passive"))
      (node (ref "J8") (pin "5") (pinfunction "5_5") (pintype "passive"))
      (node (ref "R16") (pin "2") (pinfunction "2_2") (pintype "passive"))
      (node (ref "U1") (pin "54") (pinfunction "PF6_54") (pintype "bidirectional"))
    )
    (net (code "6") (name "CLK{slash}RESET") (class "Default")
      (node (ref "J10") (pin "5") (pinfunction "5_5") (pintype "bidirectional"))
      (node (ref "J15") (pin "1") (pinfunction "1_1") (pintype "passive"))
      (node (ref "R6") (pin "2") (pinfunction "2_2") (pintype "passive"))
      (node (ref "SW1") (pin "B") (pinfunction "S_B") (pintype "passive"))
      (node (ref "SW1") (pin "B'") (pinfunction "S1_B'") (pintype "passive"))
      (node (ref "U1") (pin "57") (pinfunction "~{RESET}/PDI_57") (pintype "bidirectional"))
    )
    (net (code "7") (name "COOLANT") (class "Default")
      (node (ref "J6") (pin "6") (pinfunction "6_6") (pintype "passive"))
      (node (ref "R21") (pin "2") (pinfunction "2_2") (pintype "passive"))
      (node (ref "U1") (pin "41") (pinfunction "PE5_41") (pintype "bidirectional"))
    )
    (net (code "8") (name "GND") (class "Default")
      (node (ref "C1") (pin "-") (pinfunction "-_-") (pintype "passive"))
      (node (ref "C10") (pin "2") (pinfunction "2_2") (pintype "passive"))
      (node (ref "C11") (pin "2") (pinfunction "2_2") (pintype "passive"))
      (node (ref "C12") (pin "2") (pinfunction "2_2") (pintype "passive"))
      (node (ref "C13") (pin "2") (pinfunction "2_2") (pintype "passive"))
      (node (ref "C14") (pin "2") (pinfunction "2_2") (pintype "passive"))
      (node (ref "C15") (pin "2") (pinfunction "2_2") (pintype "passive"))
      (node (ref "C16") (pin "2") (pinfunction "2_2") (pintype "passive"))
      (node (ref "C18") (pin "1") (pinfunction "1_1") (pintype "passive"))
      (node (ref "C19") (pin "1") (pinfunction "1_1") (pintype "passive"))
      (node (ref "C2") (pin "-") (pinfunction "-_-") (pintype "passive"))
      (node (ref "C20") (pin "1") (pinfunction "1_1") (pintype "passive"))
      (node (ref "C21") (pin "1") (pinfunction "1_1") (pintype "passive"))
      (node (ref "C22") (pin "2") (pinfunction "2_2") (pintype "passive"))
      (node (ref "C23") (pin "2") (pinfunction "2_2") (pintype "passive"))
      (node (ref "C25") (pin "1") (pinfunction "1_1") (pintype "passive"))
      (node (ref "C26") (pin "1") (pinfunction "1_1") (pintype "passive"))
      (node (ref "C27") (pin "1") (pinfunction "1_1") (pintype "passive"))
      (node (ref "C28") (pin "1") (pinfunction "1_1") (pintype "passive"))
      (node (ref "C29") (pin "2") (pinfunction "2_2") (pintype "passive"))
      (node (ref "C3") (pin "-") (pinfunction "-_-") (pintype "passive"))
      (node (ref "C30") (pin "2") (pinfunction "2_2") (pintype "passive"))
      (node (ref "C32") (pin "1") (pinfunction "1_1") (pintype "passive"))
      (node (ref "C33") (pin "1") (pinfunction "1_1") (pintype "passive"))
      (node (ref "C34") (pin "1") (pinfunction "1_1") (pintype "passive"))
      (node (ref "C35") (pin "1") (pinfunction "1_1") (pintype "passive"))
      (node (ref "C36") (pin "2") (pinfunction "2_2") (pintype "passive"))
      (node (ref "C37") (pin "2") (pinfunction "2_2") (pintype "passive"))
      (node (ref "C39") (pin "1") (pinfunction "1_1") (pintype "passive"))
      (node (ref "C4") (pin "-") (pinfunction "-_-") (pintype "passive"))
      (node (ref "C40") (pin "1") (pinfunction "1_1") (pintype "passive"))
      (node (ref "C41") (pin "1") (pinfunction "1_1") (pintype "passive"))
      (node (ref "C42") (pin "1") (pinfunction "1_1") (pintype "passive"))
      (node (ref "C43") (pin "1") (pinfunction "1_1") (pintype "passive"))
      (node (ref "C44") (pin "1") (pinfunction "1_1") (pintype "passive"))
      (node (ref "C45") (pin "1") (pinfunction "1_1") (pintype "passive"))
      (node (ref "C46") (pin "1") (pinfunction "1_1") (pintype "passive"))
      (node (ref "C47") (pin "1") (pinfunction "1_1") (pintype "passive"))
      (node (ref "C48") (pin "1") (pinfunction "1_1") (pintype "passive"))
      (node (ref "C49") (pin "1") (pinfunction "1_1") (pintype "passive"))
      (node (ref "C5") (pin "-") (pinfunction "-_-") (pintype "passive"))
      (node (ref "C50") (pin "1") (pinfunction "1_1") (pintype "passive"))
      (node (ref "C6") (pin "-") (pinfunction "-_-") (pintype "passive"))
      (node (ref "C8") (pin "2") (pinfunction "2_2") (pintype "passive"))
      (node (ref "C9") (pin "2") (pinfunction "2_2") (pintype "passive"))
      (node (ref "D1") (pin "A") (pinfunction "A_A") (pintype "passive"))
      (node (ref "D10") (pin "C") (pinfunction "C_C") (pintype "passive"))
      (node (ref "D11") (pin "C") (pinfunction "C_C") (pintype "passive"))
      (node (ref "D12") (pin "C") (pinfunction "C_C") (pintype "passive"))
      (node (ref "D13") (pin "3") (pinfunction "3_3") (pintype "bidirectional"))
      (node (ref "D14") (pin "3") (pinfunction "3_3") (pintype "bidirectional"))
      (node (ref "D5") (pin "C") (pinfunction "C_C") (pintype "passive"))
      (node (ref "D6") (pin "C") (pinfunction "C_C") (pintype "passive"))
      (node (ref "D7") (pin "C") (pinfunction "C_C") (pintype "passive"))
      (node (ref "D8") (pin "C") (pinfunction "C_C") (pintype "passive"))
      (node (ref "D9") (pin "C") (pinfunction "C_C") (pintype "passive"))
      (node (ref "J1") (pin "1") (pinfunction "1_1") (pintype "passive"))
      (node (ref "J10") (pin "6") (pinfunction "6_6") (pintype "bidirectional"))
      (node (ref "J11") (pin "3") (pinfunction "3_3") (pintype "passive"))
      (node (ref "J13") (pin "1") (pinfunction "1_1") (pintype "passive"))
      (node (ref "J14") (pin "3") (pinfunction "3_3") (pintype "passive"))
      (node (ref "J15") (pin "2") (pinfunction "2_2") (pintype "passive"))
      (node (ref "J16") (pin "1") (pinfunction "1_1") (pintype "passive"))
      (node (ref "J17") (pin "1") (pinfunction "1_1") (pintype "passive"))
      (node (ref "J18") (pin "1") (pinfunction "1_1") (pintype "passive"))
      (node (ref "J19") (pin "1") (pinfunction "1_1") (pintype "passive"))
      (node (ref "J20") (pin "1") (pinfunction "1_1") (pintype "passive"))
      (node (ref "J6") (pin "1") (pinfunction "1_1") (pintype "passive"))
      (node (ref "J7") (pin "1") (pinfunction "1_1") (pintype "passive"))
      (node (ref "J8") (pin "1") (pinfunction "1_1") (pintype "passive"))
      (node (ref "J9") (pin "GND") (pinfunction "GND_GND") (pintype "bidirectional"))
      (node (ref "J9") (pin "GND@0") (pinfunction "GND_GND@0") (pintype "bidirectional"))
      (node (ref "J9") (pin "GND@1") (pinfunction "GND_GND@1") (pintype "bidirectional"))
      (node (ref "P1") (pin "1") (pinfunction "1_1") (pintype "passive"))
      (node (ref "P2") (pin "1") (pinfunction "1_1") (pintype "passive"))
      (node (ref "P3") (pin "1") (pinfunction "1_1") (pintype "passive"))
      (node (ref "P4") (pin "1") (pinfunction "1_1") (pintype "passive"))
      (node (ref "R1") (pin "1") (pinfunction "1_1") (pintype "passive"))
      (node (ref "R22") (pin "1") (pinfunction "1_1") (pintype "passive"))
      (node (ref "R23") (pin "1") (pinfunction "1_1") (pintype "passive"))
      (node (ref "R25") (pin "1") (pinfunction "1_1") (pintype "passive"))
      (node (ref "R27") (pin "1") (pinfunction "1_1") (pintype "passive"))
      (node (ref "R28") (pin "1") (pinfunction "1_1") (pintype "passive"))
      (node (ref "R29") (pin "1") (pinfunction "1_1") (pintype "passive"))
      (node (ref "R30") (pin "1") (pinfunction "1_1") (pintype "passive"))
      (node (ref "R32") (pin "1") (pinfunction "1_1") (pintype "passive"))
      (node (ref "R34") (pin "1") (pinfunction "1_1") (pintype "passive"))
      (node (ref "R35") (pin "1") (pinfunction "1_1") (pintype "passive"))
      (node (ref "R36") (pin "1") (pinfunction "1_1") (pintype "passive"))
      (node (ref "R37") (pin "1") (pinfunction "1_1") (pintype "passive"))
      (node (ref "R39") (pin "1") (pinfunction "1_1") (pintype "passive"))
      (node (ref "R4") (pin "1") (pinfunction "1_1") (pintype "passive"))
      (node (ref "R41") (pin "1") (pinfunction "1_1") (pintype "passive"))
      (node (ref "R42") (pin "1") (pinfunction "1_1") (pintype "passive"))
      (node (ref "R43") (pin "1") (pinfunction "1_1") (pintype "passive"))
      (node (ref "R44") (pin "1") (pinfunction "1_1") (pintype "passive"))
      (node (ref "R46") (pin "1") (pinfunction "1_1") (pintype "passive"))
      (node (ref "R49") (pin "1") (pinfunction "1_1") (pintype "passive"))
      (node (ref "R50") (pin "1") (pinfunction "1_1") (pintype "passive"))
      (node (ref "R7") (pin "1") (pinfunction "1_1") (pintype "passive"))
      (node (ref "SW1") (pin "A") (pinfunction "P_A") (pintype "passive"))
      (node (ref "SW1") (pin "A'") (pinfunction "P1_A'") (pintype "passive"))
      (node (ref "U1") (pin "14") (pinfunction "GND_14") (pintype "power_in"))
      (node (ref "U1") (pin "24") (pinfunction "GND_24") (pintype "power_in"))
      (node (ref "U1") (pin "34") (pinfunction "GND_34") (pintype "power_in"))
      (node (ref "U1") (pin "44") (pinfunction "GND_44") (pintype "power_in"))
      (node (ref "U1") (pin "52") (pinfunction "GND_52") (pintype "power_in"))
      (node (ref "U1") (pin "60") (pinfunction "GND_60") (pintype "power_in"))
      (node (ref "U2") (pin "16") (pinfunction "SRN_16") (pintype "bidirectional"))
      (node (ref "U2") (pin "21") (pinfunction "GND_21") (pintype "bidirectional"))
      (node (ref "U2") (pin "29") (pinfunction "GND_29") (pintype "bidirectional"))
      (node (ref "U2") (pin "7") (pinfunction "GND_7") (pintype "bidirectional"))
      (node (ref "U3") (pin "16") (pinfunction "SRN_16") (pintype "bidirectional"))
      (node (ref "U3") (pin "21") (pinfunction "GND_21") (pintype "bidirectional"))
      (node (ref "U3") (pin "29") (pinfunction "GND_29") (pintype "bidirectional"))
      (node (ref "U3") (pin "7") (pinfunction "GND_7") (pintype "bidirectional"))
      (node (ref "U4") (pin "16") (pinfunction "SRN_16") (pintype "bidirectional"))
      (node (ref "U4") (pin "21") (pinfunction "GND_21") (pintype "bidirectional"))
      (node (ref "U4") (pin "29") (pinfunction "GND_29") (pintype "bidirectional"))
      (node (ref "U4") (pin "7") (pinfunction "GND_7") (pintype "bidirectional"))
      (node (ref "U5") (pin "16") (pinfunction "SRN_16") (pintype "bidirectional"))
      (node (ref "U5") (pin "21") (pinfunction "GND_21") (pintype "bidirectional"))
      (node (ref "U5") (pin "29") (pinfunction "GND_29") (pintype "bidirectional"))
      (node (ref "U5") (pin "7") (pinfunction "GND_7") (pintype "bidirectional"))
      (node (ref "U6") (pin "13") (pinfunction "GND_13") (pintype "power_in"))
      (node (ref "U6") (pin "5") (pinfunction "GND_5") (pintype "power_in"))
      (node (ref "U7") (pin "5") (pinfunction "~{ON}/OFF_5") (pintype "bidirectional"))
      (node (ref "U7") (pin "6") (pinfunction "GND_6") (pintype "bidirectional"))
      (node (ref "U8") (pin "2") (pinfunction "GND_2") (pintype "input"))
    )
    (net (code "9") (name "M1A1") (class "Default")
      (node (ref "J2") (pin "1") (pinfunction "1_1") (pintype "passive"))
      (node (ref "R52") (pin "2") (pinfunction "2_2") (pintype "passive"))
      (node (ref "U2") (pin "4") (pinfunction "AOUT1_4") (pintype "bidirectional"))
    )
    (net (code "10") (name "M1A2") (class "Default")
      (node (ref "J2") (pin "2") (pinfunction "2_2") (pintype "passive"))
      (node (ref "U2") (pin "25") (pinfunction "AOUT2_25") (pintype "bidirectional"))
    )
    (net (code "11") (name "M1B1") (class "Default")
      (node (ref "J2") (pin "3") (pinfunction "3_3") (pintype "passive"))
      (node (ref "U2") (pin "11") (pinfunction "BOUT1_11") (pintype "bidirectional"))
    )
    (net (code "12") (name "M1B2") (class "Default")
      (node (ref "J2") (pin "4") (pinfunction "4_4") (pintype "passive"))
      (node (ref "U2") (pin "18") (pinfunction "BOUT2_18") (pintype "bidirectional"))
    )
    (net (code "13") (name "M2A1") (class "Default")
      (node (ref "J3") (pin "1") (pinfunction "1_1") (pintype "passive"))
      (node (ref "R53") (pin "2") (pinfunction "2_2") (pintype "passive"))
      (node (ref "U3") (pin "4") (pinfunction "AOUT1_4") (pintype "bidirectional"))
    )
    (net (code "14") (name "M2A2") (class "Default")
      (node (ref "J3") (pin "2") (pinfunction "2_2") (pintype "passive"))
      (node (ref "U3") (pin "25") (pinfunction "AOUT2_25") (pintype "bidirectional"))
    )
    (net (code "15") (name "M2B1") (class "Default")
      (node (ref "J3") (pin "3") (pinfunction "3_3") (pintype "passive"))
      (node (ref "U3") (pin "11") (pinfunction "BOUT1_11") (pintype "bidirectional"))
    )
    (net (code "16") (name "M2B2") (class "Default")
      (node (ref "J3") (pin "4") (pinfunction "4_4") (pintype "passive"))
      (node (ref "U3") (pin "18") (pinfunction "BOUT2_18") (pintype "bidirectional"))
    )
    (net (code "17") (name "M3A1") (class "Default")
      (node (ref "J4") (pin "1") (pinfunction "1_1") (pintype "passive"))
      (node (ref "R51") (pin "2") (pinfunction "2_2") (pintype "passive"))
      (node (ref "U4") (pin "4") (pinfunction "AOUT1_4") (pintype "bidirectional"))
    )
    (net (code "18") (name "M3A2") (class "Default")
      (node (ref "J4") (pin "2") (pinfunction "2_2") (pintype "passive"))
      (node (ref "U4") (pin "25") (pinfunction "AOUT2_25") (pintype "bidirectional"))
    )
    (net (code "19") (name "M3B1") (class "Default")
      (node (ref "J4") (pin "3") (pinfunction "3_3") (pintype "passive"))
      (node (ref "U4") (pin "11") (pinfunction "BOUT1_11") (pintype "bidirectional"))
    )
    (net (code "20") (name "M3B2") (class "Default")
      (node (ref "J4") (pin "4") (pinfunction "4_4") (pintype "passive"))
      (node (ref "U4") (pin "18") (pinfunction "BOUT2_18") (pintype "bidirectional"))
    )
    (net (code "21") (name "M4A1") (class "Default")
      (node (ref "J5") (pin "1") (pinfunction "1_1") (pintype "passive"))
      (node (ref "R48") (pin "2") (pinfunction "2_2") (pintype "passive"))
      (node (ref "U5") (pin "4") (pinfunction "AOUT1_4") (pintype "bidirectional"))
    )
    (net (code "22") (name "M4A2") (class "Default")
      (node (ref "J5") (pin "2") (pinfunction "2_2") (pintype "passive"))
      (node (ref "U5") (pin "25") (pinfunction "AOUT2_25") (pintype "bidirectional"))
    )
    (net (code "23") (name "M4B1") (class "Default")
      (node (ref "J5") (pin "3") (pinfunction "3_3") (pintype "passive"))
      (node (ref "U5") (pin "11") (pinfunction "BOUT1_11") (pintype "bidirectional"))
    )
    (net (code "24") (name "M4B2") (class "Default")
      (node (ref "J5") (pin "4") (pinfunction "4_4") (pintype "passive"))
      (node (ref "U5") (pin "18") (pinfunction "BOUT2_18") (pintype "bidirectional"))
    )
    (net (code "25") (name "MISO") (class "Default")
      (node (ref "J13") (pin "5") (pinfunction "5_5") (pintype "passive"))
      (node (ref "U1") (pin "22") (pinfunction "PC6_22") (pintype "bidirectional"))
    )
    (net (code "26") (name "MOSI") (class "Default")
      (node (ref "J13") (pin "4") (pinfunction "4_4") (pintype "passive"))
      (node (ref "U1") (pin "21") (pinfunction "PC5_21") (pintype "bidirectional"))
    )
    (net (code "27") (name "Net-(D2-PadC)") (class "Default")
      (node (ref "D2") (pin "C") (pinfunction "C_C") (pintype "passive"))
      (node (ref "R1") (pin "2") (pinfunction "2_2") (pintype "passive"))
    )
    (net (code "28") (name "Net-(D3-PadC)") (class "Default")
      (node (ref "D3") (pin "C") (pinfunction "C_C") (pintype "passive"))
      (node (ref "R2") (pin "2") (pinfunction "2_2") (pintype "passive"))
    )
    (net (code "29") (name "Net-(D4-PadC)") (class "Default")
      (node (ref "D4") (pin "C") (pinfunction "C_C") (pintype "passive"))
      (node (ref "R3") (pin "2") (pinfunction "2_2") (pintype "passive"))
    )
    (net (code "30") (name "Net-(D5-PadA)") (class "Default")
      (node (ref "D5") (pin "A") (pinfunction "A_A") (pintype "passive"))
      (node (ref "R18") (pin "1") (pinfunction "1_1") (pintype "passive"))
    )
    (net (code "31") (name "Net-(D6-PadA)") (class "Default")
      (node (ref "D6") (pin "A") (pinfunction "A_A") (pintype "passive"))
      (node (ref "R19") (pin "1") (pinfunction "1_1") (pintype "passive"))
    )
    (net (code "32") (name "Net-(D7-PadA)") (class "Default")
      (node (ref "D7") (pin "A") (pinfunction "A_A") (pintype "passive"))
      (node (ref "R20") (pin "1") (pinfunction "1_1") (pintype "passive"))
    )
    (net (code "33") (name "Net-(D8-PadA)") (class "Default")
      (node (ref "D8") (pin "A") (pinfunction "A_A") (pintype "passive"))
      (node (ref "R21") (pin "1") (pinfunction "1_1") (pintype "passive"))
    )
    (net (code "34") (name "Net-(D9-PadA)") (class "Default")
      (node (ref "D9") (pin "A") (pinfunction "A_A") (pintype "passive"))
      (node (ref "R52") (pin "1") (pinfunction "1_1") (pintype "passive"))
    )
    (net (code "35") (name "Net-(D10-PadA)") (class "Default")
      (node (ref "D10") (pin "A") (pinfunction "A_A") (pintype "passive"))
      (node (ref "R53") (pin "1") (pinfunction "1_1") (pintype "passive"))
    )
    (net (code "36") (name "Net-(D11-PadA)") (class "Default")
      (node (ref "D11") (pin "A") (pinfunction "A_A") (pintype "passive"))
      (node (ref "R51") (pin "1") (pinfunction "1_1") (pintype "passive"))
    )
    (net (code "37") (name "Net-(D12-PadA)") (class "Default")
      (node (ref "D12") (pin "A") (pinfunction "A_A") (pintype "passive"))
      (node (ref "R48") (pin "1") (pinfunction "1_1") (pintype "passive"))
    )
    (net (code "38") (name "Net-(J11-Pad2)") (class "Default")
      (node (ref "J11") (pin "2") (pinfunction "2_2") (pintype "passive"))
      (node (ref "J12") (pin "2") (pinfunction "2_2") (pintype "passive"))
    )
    (net (code "39") (name "Net-(P1-Pad3)") (class "Default")
      (node (ref "P1") (pin "3") (pinfunction "3_3") (pintype "passive"))
      (node (ref "R26") (pin "2") (pinfunction "2_2") (pintype "passive"))
    )
    (net (code "40") (name "Net-(P2-Pad3)") (class "Default")
      (node (ref "P2") (pin "3") (pinfunction "3_3") (pintype "passive"))
      (node (ref "R33") (pin "2") (pinfunction "2_2") (pintype "passive"))
    )
    (net (code "41") (name "Net-(P3-Pad3)") (class "Default")
      (node (ref "P3") (pin "3") (pinfunction "3_3") (pintype "passive"))
      (node (ref "R40") (pin "2") (pinfunction "2_2") (pintype "passive"))
    )
    (net (code "42") (name "Net-(P4-Pad3)") (class "Default")
      (node (ref "P4") (pin "3") (pinfunction "3_3") (pintype "passive"))
      (node (ref "R47") (pin "2") (pinfunction "2_2") (pintype "passive"))
    )
    (net (code "43") (name "Net-(U1-PB0)") (class "Default")
      (node (ref "J16") (pin "2") (pinfunction "2_2") (pintype "passive"))
      (node (ref "U1") (pin "6") (pinfunction "PB0_6") (pintype "bidirectional"))
    )
    (net (code "44") (name "Net-(U1-PC0)") (class "Default")
      (node (ref "U1") (pin "16") (pinfunction "PC0_16") (pintype "bidirectional"))
      (node (ref "U6") (pin "6") (pinfunction "~{CTS}_6") (pintype "input"))
    )
    (net (code "45") (name "Net-(U1-PC1)") (class "Default")
      (node (ref "U1") (pin "17") (pinfunction "PC1_17") (pintype "bidirectional"))
      (node (ref "U6") (pin "2") (pinfunction "~{RTS}_2") (pintype "output"))
    )
    (net (code "46") (name "Net-(U1-PC2)") (class "Default")
      (node (ref "R7") (pin "2") (pinfunction "2_2") (pintype "passive"))
      (node (ref "R8") (pin "1") (pinfunction "1_1") (pintype "passive"))
      (node (ref "R9") (pin "1") (pinfunction "1_1") (pintype "passive"))
      (node (ref "U1") (pin "18") (pinfunction "PC2_18") (pintype "bidirectional"))
    )
    (net (code "47") (name "Net-(U1-PR0)") (class "Default")
      (node (ref "C9") (pin "1") (pinfunction "1_1") (pintype "passive"))
      (node (ref "U1") (pin "58") (pinfunction "PR0_58") (pintype "bidirectional"))
      (node (ref "X1") (pin "2") (pinfunction "2_2") (pintype "bidirectional"))
    )
    (net (code "48") (name "Net-(U1-PR1)") (class "Default")
      (node (ref "C8") (pin "1") (pinfunction "1_1") (pintype "passive"))
      (node (ref "U1") (pin "59") (pinfunction "PR1_59") (pintype "bidirectional"))
      (node (ref "X1") (pin "1") (pinfunction "1_1") (pintype "bidirectional"))
    )
    (net (code "49") (name "Net-(U2-CP1)") (class "Default")
      (node (ref "C17") (pin "2") (pinfunction "2_2") (pintype "passive"))
      (node (ref "U2") (pin "23") (pinfunction "CP1_23") (pintype "bidirectional"))
    )
    (net (code "50") (name "Net-(U2-CP2)") (class "Default")
      (node (ref "C17") (pin "1") (pinfunction "1_1") (pintype "passive"))
      (node (ref "U2") (pin "24") (pinfunction "CP2_24") (pintype "bidirectional"))
    )
    (net (code "51") (name "Net-(U2-DECAY)") (class "Default")
      (node (ref "C18") (pin "2") (pinfunction "2_2") (pintype "passive"))
      (node (ref "R24") (pin "2") (pinfunction "2_2") (pintype "passive"))
      (node (ref "R25") (pin "2") (pinfunction "2_2") (pintype "passive"))
      (node (ref "U2") (pin "5") (pinfunction "DECAY_5") (pintype "bidirectional"))
    )
    (net (code "52") (name "Net-(U2-ISENA)") (class "Default")
      (node (ref "R22") (pin "2") (pinfunction "2_2") (pintype "passive"))
      (node (ref "U2") (pin "1") (pinfunction "ISENA_1") (pintype "bidirectional"))
    )
    (net (code "53") (name "Net-(U2-ISENB)") (class "Default")
      (node (ref "R23") (pin "2") (pinfunction "2_2") (pintype "passive"))
      (node (ref "U2") (pin "14") (pinfunction "ISENB_14") (pintype "bidirectional"))
    )
    (net (code "54") (name "Net-(U2-RCA)") (class "Default")
      (node (ref "C20") (pin "2") (pinfunction "2_2") (pintype "passive"))
      (node (ref "R27") (pin "2") (pinfunction "2_2") (pintype "passive"))
      (node (ref "U2") (pin "6") (pinfunction "RCA_6") (pintype "bidirectional"))
    )
    (net (code "55") (name "Net-(U2-RCB)") (class "Default")
      (node (ref "C21") (pin "2") (pinfunction "2_2") (pintype "passive"))
      (node (ref "R28") (pin "2") (pinfunction "2_2") (pintype "passive"))
      (node (ref "U2") (pin "9") (pinfunction "RCB_9") (pintype "bidirectional"))
    )
    (net (code "56") (name "Net-(U2-VCP)") (class "Default")
      (node (ref "C16") (pin "1") (pinfunction "1_1") (pintype "passive"))
      (node (ref "U2") (pin "22") (pinfunction "VCP_22") (pintype "bidirectional"))
    )
    (net (code "57") (name "Net-(U2-VGD)") (class "Default")
      (node (ref "C15") (pin "1") (pinfunction "1_1") (pintype "passive"))
      (node (ref "U2") (pin "20") (pinfunction "VGD_20") (pintype "bidirectional"))
    )
    (net (code "58") (name "Net-(U2-VREF)") (class "Default")
      (node (ref "P1") (pin "2") (pinfunction "2_2") (pintype "passive"))
      (node (ref "U2") (pin "8") (pinfunction "VREF_8") (pintype "bidirectional"))
    )
    (net (code "59") (name "Net-(U3-CP1)") (class "Default")
      (node (ref "C24") (pin "2") (pinfunction "2_2") (pintype "passive"))
      (node (ref "U3") (pin "23") (pinfunction "CP1_23") (pintype "bidirectional"))
    )
    (net (code "60") (name "Net-(U3-CP2)") (class "Default")
      (node (ref "C24") (pin "1") (pinfunction "1_1") (pintype "passive"))
      (node (ref "U3") (pin "24") (pinfunction "CP2_24") (pintype "bidirectional"))
    )
    (net (code "61") (name "Net-(U3-DECAY)") (class "Default")
      (node (ref "C25") (pin "2") (pinfunction "2_2") (pintype "passive"))
      (node (ref "R31") (pin "2") (pinfunction "2_2") (pintype "passive"))
      (node (ref "R32") (pin "2") (pinfunction "2_2") (pintype "passive"))
      (node (ref "U3") (pin "5") (pinfunction "DECAY_5") (pintype "bidirectional"))
    )
    (net (code "62") (name "Net-(U3-ISENA)") (class "Default")
      (node (ref "R29") (pin "2") (pinfunction "2_2") (pintype "passive"))
      (node (ref "U3") (pin "1") (pinfunction "ISENA_1") (pintype "bidirectional"))
    )
    (net (code "63") (name "Net-(U3-ISENB)") (class "Default")
      (node (ref "R30") (pin "2") (pinfunction "2_2") (pintype "passive"))
      (node (ref "U3") (pin "14") (pinfunction "ISENB_14") (pintype "bidirectional"))
    )
    (net (code "64") (name "Net-(U3-RCA)") (class "Default")
      (node (ref "C27") (pin "2") (pinfunction "2_2") (pintype "passive"))
      (node (ref "R34") (pin "2") (pinfunction "2_2") (pintype "passive"))
      (node (ref "U3") (pin "6") (pinfunction "RCA_6") (pintype "bidirectional"))
    )
    (net (code "65") (name "Net-(U3-RCB)") (class "Default")
      (node (ref "C28") (pin "2") (pinfunction "2_2") (pintype "passive"))
      (node (ref "R35") (pin "2") (pinfunction "2_2") (pintype "passive"))
      (node (ref "U3") (pin "9") (pinfunction "RCB_9") (pintype "bidirectional"))
    )
    (net (code "66") (name "Net-(U3-VCP)") (class "Default")
      (node (ref "C23") (pin "1") (pinfunction "1_1") (pintype "passive"))
      (node (ref "U3") (pin "22") (pinfunction "VCP_22") (pintype "bidirectional"))
    )
    (net (code "67") (name "Net-(U3-VGD)") (class "Default")
      (node (ref "C22") (pin "1") (pinfunction "1_1") (pintype "passive"))
      (node (ref "U3") (pin "20") (pinfunction "VGD_20") (pintype "bidirectional"))
    )
    (net (code "68") (name "Net-(U3-VREF)") (class "Default")
      (node (ref "P2") (pin "2") (pinfunction "2_2") (pintype "passive"))
      (node (ref "U3") (pin "8") (pinfunction "VREF_8") (pintype "bidirectional"))
    )
    (net (code "69") (name "Net-(U4-CP1)") (class "Default")
      (node (ref "C31") (pin "2") (pinfunction "2_2") (pintype "passive"))
      (node (ref "U4") (pin "23") (pinfunction "CP1_23") (pintype "bidirectional"))
    )
    (net (code "70") (name "Net-(U4-CP2)") (class "Default")
      (node (ref "C31") (pin "1") (pinfunction "1_1") (pintype "passive"))
      (node (ref "U4") (pin "24") (pinfunction "CP2_24") (pintype "bidirectional"))
    )
    (net (code "71") (name "Net-(U4-DECAY)") (class "Default")
      (node (ref "C32") (pin "2") (pinfunction "2_2") (pintype "passive"))
      (node (ref "R38") (pin "2") (pinfunction "2_2") (pintype "passive"))
      (node (ref "R39") (pin "2") (pinfunction "2_2") (pintype "passive"))
      (node (ref "U4") (pin "5") (pinfunction "DECAY_5") (pintype "bidirectional"))
    )
    (net (code "72") (name "Net-(U4-ISENA)") (class "Default")
      (node (ref "R36") (pin "2") (pinfunction "2_2") (pintype "passive"))
      (node (ref "U4") (pin "1") (pinfunction "ISENA_1") (pintype "bidirectional"))
    )
    (net (code "73") (name "Net-(U4-ISENB)") (class "Default")
      (node (ref "R37") (pin "2") (pinfunction "2_2") (pintype "passive"))
      (node (ref "U4") (pin "14") (pinfunction "ISENB_14") (pintype "bidirectional"))
    )
    (net (code "74") (name "Net-(U4-RCA)") (class "Default")
      (node (ref "C34") (pin "2") (pinfunction "2_2") (pintype "passive"))
      (node (ref "R41") (pin "2") (pinfunction "2_2") (pintype "passive"))
      (node (ref "U4") (pin "6") (pinfunction "RCA_6") (pintype "bidirectional"))
    )
    (net (code "75") (name "Net-(U4-RCB)") (class "Default")
      (node (ref "C35") (pin "2") (pinfunction "2_2") (pintype "passive"))
      (node (ref "R42") (pin "2") (pinfunction "2_2") (pintype "passive"))
      (node (ref "U4") (pin "9") (pinfunction "RCB_9") (pintype "bidirectional"))
    )
    (net (code "76") (name "Net-(U4-VCP)") (class "Default")
      (node (ref "C30") (pin "1") (pinfunction "1_1") (pintype "passive"))
      (node (ref "U4") (pin "22") (pinfunction "VCP_22") (pintype "bidirectional"))
    )
    (net (code "77") (name "Net-(U4-VGD)") (class "Default")
      (node (ref "C29") (pin "1") (pinfunction "1_1") (pintype "passive"))
      (node (ref "U4") (pin "20") (pinfunction "VGD_20") (pintype "bidirectional"))
    )
    (net (code "78") (name "Net-(U4-VREF)") (class "Default")
      (node (ref "P3") (pin "2") (pinfunction "2_2") (pintype "passive"))
      (node (ref "U4") (pin "8") (pinfunction "VREF_8") (pintype "bidirectional"))
    )
    (net (code "79") (name "Net-(U5-CP1)") (class "Default")
      (node (ref "C38") (pin "2") (pinfunction "2_2") (pintype "passive"))
      (node (ref "U5") (pin "23") (pinfunction "CP1_23") (pintype "bidirectional"))
    )
    (net (code "80") (name "Net-(U5-CP2)") (class "Default")
      (node (ref "C38") (pin "1") (pinfunction "1_1") (pintype "passive"))
      (node (ref "U5") (pin "24") (pinfunction "CP2_24") (pintype "bidirectional"))
    )
    (net (code "81") (name "Net-(U5-DECAY)") (class "Default")
      (node (ref "C39") (pin "2") (pinfunction "2_2") (pintype "passive"))
      (node (ref "R45") (pin "2") (pinfunction "2_2") (pintype "passive"))
      (node (ref "R46") (pin "2") (pinfunction "2_2") (pintype "passive"))
      (node (ref "U5") (pin "5") (pinfunction "DECAY_5") (pintype "bidirectional"))
    )
    (net (code "82") (name "Net-(U5-ISENA)") (class "Default")
      (node (ref "R43") (pin "2") (pinfunction "2_2") (pintype "passive"))
      (node (ref "U5") (pin "1") (pinfunction "ISENA_1") (pintype "bidirectional"))
    )
    (net (code "83") (name "Net-(U5-ISENB)") (class "Default")
      (node (ref "R44") (pin "2") (pinfunction "2_2") (pintype "passive"))
      (node (ref "U5") (pin "14") (pinfunction "ISENB_14") (pintype "bidirectional"))
    )
    (net (code "84") (name "Net-(U5-RCA)") (class "Default")
      (node (ref "C41") (pin "2") (pinfunction "2_2") (pintype "passive"))
      (node (ref "R49") (pin "2") (pinfunction "2_2") (pintype "passive"))
      (node (ref "U5") (pin "6") (pinfunction "RCA_6") (pintype "bidirectional"))
    )
    (net (code "85") (name "Net-(U5-RCB)") (class "Default")
      (node (ref "C42") (pin "2") (pinfunction "2_2") (pintype "passive"))
      (node (ref "R50") (pin "2") (pinfunction "2_2") (pintype "passive"))
      (node (ref "U5") (pin "9") (pinfunction "RCB_9") (pintype "bidirectional"))
    )
    (net (code "86") (name "Net-(U5-VCP)") (class "Default")
      (node (ref "C37") (pin "1") (pinfunction "1_1") (pintype "passive"))
      (node (ref "U5") (pin "22") (pinfunction "VCP_22") (pintype "bidirectional"))
    )
    (net (code "87") (name "Net-(U5-VGD)") (class "Default")
      (node (ref "C36") (pin "1") (pinfunction "1_1") (pintype "passive"))
      (node (ref "U5") (pin "20") (pinfunction "VGD_20") (pintype "bidirectional"))
    )
    (net (code "88") (name "Net-(U5-VREF)") (class "Default")
      (node (ref "P4") (pin "2") (pinfunction "2_2") (pintype "passive"))
      (node (ref "U5") (pin "8") (pinfunction "VREF_8") (pintype "bidirectional"))
    )
    (net (code "89") (name "Net-(U6-CBUS1)") (class "Default")
      (node (ref "R3") (pin "1") (pinfunction "1_1") (pintype "passive"))
      (node (ref "U6") (pin "14") (pinfunction "CBUS1_14") (pintype "bidirectional"))
    )
    (net (code "90") (name "Net-(U6-CBUS2)") (class "Default")
      (node (ref "R2") (pin "1") (pinfunction "1_1") (pintype "passive"))
      (node (ref "U6") (pin "7") (pinfunction "CBUS2_7") (pintype "bidirectional"))
    )
    (net (code "91") (name "Net-(U6-TXD)") (class "Default")
      (node (ref "R9") (pin "2") (pinfunction "2_2") (pintype "passive"))
      (node (ref "U6") (pin "1") (pinfunction "TXD_1") (pintype "output"))
    )
    (net (code "92") (name "Net-(U6-USBDM)") (class "Default")
      (node (ref "D14") (pin "2") (pinfunction "2_2") (pintype "power_in"))
      (node (ref "J9") (pin "D-") (pinfunction "D-_D-") (pintype "bidirectional"))
      (node (ref "U6") (pin "9") (pinfunction "USBDM_9") (pintype "input"))
    )
    (net (code "93") (name "Net-(U6-USBDP)") (class "Default")
      (node (ref "D14") (pin "1") (pinfunction "1_1") (pintype "power_in"))
      (node (ref "J9") (pin "D+") (pinfunction "D+_D+") (pintype "bidirectional"))
      (node (ref "U6") (pin "8") (pinfunction "USBDP_8") (pintype "input"))
    )
    (net (code "94") (name "Net-(U7-FB)") (class "Default")
      (node (ref "C7") (pin "1") (pinfunction "1_1") (pintype "passive"))
      (node (ref "R4") (pin "2") (pinfunction "2_2") (pintype "passive"))
      (node (ref "R5") (pin "2") (pinfunction "2_2") (pintype "passive"))
      (node (ref "U7") (pin "4") (pinfunction "FB_4") (pintype "bidirectional"))
    )
    (net (code "95") (name "Net-(U7-OUTPUT)") (class "Default")
      (node (ref "D1") (pin "C") (pinfunction "C_C") (pintype "passive"))
      (node (ref "L1") (pin "1") (pinfunction "1_1") (pintype "bidirectional"))
      (node (ref "U7") (pin "8") (pinfunction "OUTPUT_8") (pintype "bidirectional"))
    )
    (net (code "96") (name "PA0") (class "Default")
      (node (ref "J17") (pin "2") (pinfunction "2_2") (pintype "passive"))
      (node (ref "U1") (pin "62") (pinfunction "PA0_62") (pintype "bidirectional"))
      (node (ref "U2") (pin "19") (pinfunction "STEP_19") (pintype "bidirectional"))
    )
    (net (code "97") (name "PA1") (class "Default")
      (node (ref "J17") (pin "3") (pinfunction "3_3") (pintype "passive"))
      (node (ref "U1") (pin "63") (pinfunction "PA1_63") (pintype "bidirectional"))
      (node (ref "U2") (pin "3") (pinfunction "DIR_3") (pintype "bidirectional"))
    )
    (net (code "98") (name "PA2") (class "Default")
      (node (ref "J17") (pin "4") (pinfunction "4_4") (pintype "passive"))
      (node (ref "U1") (pin "64") (pinfunction "PA2_64") (pintype "bidirectional"))
      (node (ref "U2") (pin "26") (pinfunction "ENABLEN_26") (pintype "bidirectional"))
    )
    (net (code "99") (name "PA3") (class "Default")
      (node (ref "U1") (pin "1") (pinfunction "PA3_1") (pintype "bidirectional"))
      (node (ref "U2") (pin "13") (pinfunction "USM0_13") (pintype "bidirectional"))
    )
    (net (code "100") (name "PA4") (class "Default")
      (node (ref "U1") (pin "2") (pinfunction "PA4_2") (pintype "bidirectional"))
      (node (ref "U2") (pin "12") (pinfunction "USM1_12") (pintype "bidirectional"))
    )
    (net (code "101") (name "PD0") (class "Default")
      (node (ref "J20") (pin "2") (pinfunction "2_2") (pintype "passive"))
      (node (ref "U1") (pin "26") (pinfunction "PD0_26") (pintype "bidirectional"))
      (node (ref "U5") (pin "19") (pinfunction "STEP_19") (pintype "bidirectional"))
    )
    (net (code "102") (name "PD1") (class "Default")
      (node (ref "J20") (pin "3") (pinfunction "3_3") (pintype "passive"))
      (node (ref "U1") (pin "27") (pinfunction "PD1_27") (pintype "bidirectional"))
      (node (ref "U5") (pin "3") (pinfunction "DIR_3") (pintype "bidirectional"))
    )
    (net (code "103") (name "PD2") (class "Default")
      (node (ref "J20") (pin "4") (pinfunction "4_4") (pintype "passive"))
      (node (ref "U1") (pin "28") (pinfunction "PD2_28") (pintype "bidirectional"))
      (node (ref "U5") (pin "26") (pinfunction "ENABLEN_26") (pintype "bidirectional"))
    )
    (net (code "104") (name "PD3") (class "Default")
      (node (ref "U1") (pin "29") (pinfunction "PD3_29") (pintype "bidirectional"))
      (node (ref "U5") (pin "13") (pinfunction "USM0_13") (pintype "bidirectional"))
    )
    (net (code "105") (name "PD4") (class "Default")
      (node (ref "U1") (pin "30") (pinfunction "PD4_30") (pintype "bidirectional"))
      (node (ref "U5") (pin "12") (pinfunction "USM1_12") (pintype "bidirectional"))
    )
    (net (code "106") (name "PDI") (class "Default")
      (node (ref "J10") (pin "1") (pinfunction "1_1") (pintype "bidirectional"))
      (node (ref "U1") (pin "56") (pinfunction "PDI_56") (pintype "bidirectional"))
    )
    (net (code "107") (name "PE0") (class "Default")
      (node (ref "J19") (pin "2") (pinfunction "2_2") (pintype "passive"))
      (node (ref "U1") (pin "36") (pinfunction "PE0_36") (pintype "bidirectional"))
      (node (ref "U4") (pin "19") (pinfunction "STEP_19") (pintype "bidirectional"))
    )
    (net (code "108") (name "PE1") (class "Default")
      (node (ref "J19") (pin "3") (pinfunction "3_3") (pintype "passive"))
      (node (ref "U1") (pin "37") (pinfunction "PE1_37") (pintype "bidirectional"))
      (node (ref "U4") (pin "3") (pinfunction "DIR_3") (pintype "bidirectional"))
    )
    (net (code "109") (name "PE2") (class "Default")
      (node (ref "J19") (pin "4") (pinfunction "4_4") (pintype "passive"))
      (node (ref "U1") (pin "38") (pinfunction "PE2_38") (pintype "bidirectional"))
      (node (ref "U4") (pin "26") (pinfunction "ENABLEN_26") (pintype "bidirectional"))
    )
    (net (code "110") (name "PE3") (class "Default")
      (node (ref "U1") (pin "39") (pinfunction "PE3_39") (pintype "bidirectional"))
      (node (ref "U4") (pin "13") (pinfunction "USM0_13") (pintype "bidirectional"))
    )
    (net (code "111") (name "PE4") (class "Default")
      (node (ref "U1") (pin "40") (pinfunction "PE4_40") (pintype "bidirectional"))
      (node (ref "U4") (pin "12") (pinfunction "USM1_12") (pintype "bidirectional"))
    )
    (net (code "112") (name "PF0") (class "Default")
      (node (ref "J18") (pin "2") (pinfunction "2_2") (pintype "passive"))
      (node (ref "U1") (pin "46") (pinfunction "PF0_46") (pintype "bidirectional"))
      (node (ref "U3") (pin "19") (pinfunction "STEP_19") (pintype "bidirectional"))
    )
    (net (code "113") (name "PF1") (class "Default")
      (node (ref "J18") (pin "3") (pinfunction "3_3") (pintype "passive"))
      (node (ref "U1") (pin "47") (pinfunction "PF1_47") (pintype "bidirectional"))
      (node (ref "U3") (pin "3") (pinfunction "DIR_3") (pintype "bidirectional"))
    )
    (net (code "114") (name "PF2") (class "Default")
      (node (ref "J18") (pin "4") (pinfunction "4_4") (pintype "passive"))
      (node (ref "U1") (pin "48") (pinfunction "PF2_48") (pintype "bidirectional"))
      (node (ref "U3") (pin "26") (pinfunction "ENABLEN_26") (pintype "bidirectional"))
    )
    (net (code "115") (name "PF3") (class "Default")
      (node (ref "U1") (pin "49") (pinfunction "PF3_49") (pintype "bidirectional"))
      (node (ref "U3") (pin "13") (pinfunction "USM0_13") (pintype "bidirectional"))
    )
    (net (code "116") (name "PF4") (class "Default")
      (node (ref "U1") (pin "50") (pinfunction "PF4_50") (pintype "bidirectional"))
      (node (ref "U3") (pin "12") (pinfunction "USM1_12") (pintype "bidirectional"))
    )
    (net (code "117") (name "RX") (class "Default")
      (node (ref "J14") (pin "2") (pinfunction "2_2") (pintype "passive"))
      (node (ref "R8") (pin "2") (pinfunction "2_2") (pintype "passive"))
    )
    (net (code "118") (name "SCK") (class "Default")
      (node (ref "J13") (pin "6") (pinfunction "6_6") (pintype "passive"))
      (node (ref "U1") (pin "23") (pinfunction "PC7_23") (pintype "bidirectional"))
    )
    (net (code "119") (name "SPINDIR") (class "Default")
      (node (ref "J6") (pin "4") (pinfunction "4_4") (pintype "passive"))
      (node (ref "R19") (pin "2") (pinfunction "2_2") (pintype "passive"))
      (node (ref "U1") (pin "51") (pinfunction "PF5_51") (pintype "bidirectional"))
    )
    (net (code "120") (name "SPINDLE") (class "Default")
      (node (ref "J6") (pin "3") (pinfunction "3_3") (pintype "passive"))
      (node (ref "R18") (pin "2") (pinfunction "2_2") (pintype "passive"))
      (node (ref "U1") (pin "3") (pinfunction "PA5_3") (pintype "bidirectional"))
    )
    (net (code "121") (name "SPINPWM") (class "Default")
      (node (ref "J6") (pin "5") (pinfunction "5_5") (pintype "passive"))
      (node (ref "R20") (pin "2") (pinfunction "2_2") (pintype "passive"))
      (node (ref "U1") (pin "31") (pinfunction "PD5_31") (pintype "bidirectional"))
    )
    (net (code "122") (name "TX") (class "Default")
      (node (ref "J14") (pin "1") (pinfunction "1_1") (pintype "passive"))
      (node (ref "U1") (pin "19") (pinfunction "PC3_19") (pintype "bidirectional"))
      (node (ref "U6") (pin "4") (pinfunction "RXD_4") (pintype "input"))
    )
    (net (code "123") (name "XMAX") (class "Default")
      (node (ref "C44") (pin "2") (pinfunction "2_2") (pintype "passive"))
      (node (ref "J7") (pin "4") (pinfunction "4_4") (pintype "passive"))
      (node (ref "R11") (pin "2") (pinfunction "2_2") (pintype "passive"))
      (node (ref "U1") (pin "5") (pinfunction "PA7_5") (pintype "bidirectional"))
    )
    (net (code "124") (name "XMIN") (class "Default")
      (node (ref "C43") (pin "2") (pinfunction "2_2") (pintype "passive"))
      (node (ref "J7") (pin "3") (pinfunction "3_3") (pintype "passive"))
      (node (ref "R10") (pin "2") (pinfunction "2_2") (pintype "passive"))
      (node (ref "U1") (pin "4") (pinfunction "PA6_4") (pintype "bidirectional"))
    )
    (net (code "125") (name "YMAX") (class "Default")
      (node (ref "C46") (pin "2") (pinfunction "2_2") (pintype "passive"))
      (node (ref "J7") (pin "6") (pinfunction "6_6") (pintype "passive"))
      (node (ref "R13") (pin "2") (pinfunction "2_2") (pintype "passive"))
      (node (ref "U1") (pin "33") (pinfunction "PD7_33") (pintype "bidirectional"))
    )
    (net (code "126") (name "YMIN") (class "Default")
      (node (ref "C45") (pin "2") (pinfunction "2_2") (pintype "passive"))
      (node (ref "J7") (pin "5") (pinfunction "5_5") (pintype "passive"))
      (node (ref "R12") (pin "2") (pinfunction "2_2") (pintype "passive"))
      (node (ref "U1") (pin "32") (pinfunction "PD6_32") (pintype "bidirectional"))
    )
    (net (code "127") (name "ZMAX") (class "Default")
      (node (ref "C48") (pin "2") (pinfunction "2_2") (pintype "passive"))
      (node (ref "J8") (pin "4") (pinfunction "4_4") (pintype "passive"))
      (node (ref "R15") (pin "2") (pinfunction "2_2") (pintype "passive"))
      (node (ref "U1") (pin "43") (pinfunction "PE7_43") (pintype "bidirectional"))
    )
    (net (code "128") (name "ZMIN") (class "Default")
      (node (ref "C47") (pin "2") (pinfunction "2_2") (pintype "passive"))
      (node (ref "J8") (pin "3") (pinfunction "3_3") (pintype "passive"))
      (node (ref "R14") (pin "2") (pinfunction "2_2") (pintype "passive"))
      (node (ref "U1") (pin "42") (pinfunction "PE6_42") (pintype "bidirectional"))
    )
    (net (code "129") (name "unconnected-(J9-PadVBUS)") (class "Default")
      (node (ref "J9") (pin "VBUS") (pinfunction "VBUS_VBUS") (pintype "bidirectional"))
    )
    (net (code "130") (name "unconnected-(J10-Pad3)") (class "Default")
      (node (ref "J10") (pin "3") (pinfunction "3_3") (pintype "bidirectional"))
    )
    (net (code "131") (name "unconnected-(J10-Pad4)") (class "Default")
      (node (ref "J10") (pin "4") (pinfunction "4_4") (pintype "bidirectional"))
    )
    (net (code "132") (name "unconnected-(J11-Pad1)") (class "Default")
      (node (ref "J11") (pin "1") (pinfunction "1_1") (pintype "passive"))
    )
    (net (code "133") (name "unconnected-(U1-PB1-Pad7)") (class "Default")
      (node (ref "U1") (pin "7") (pinfunction "PB1_7") (pintype "bidirectional"))
    )
    (net (code "134") (name "unconnected-(U1-PB2-Pad8)") (class "Default")
      (node (ref "U1") (pin "8") (pinfunction "PB2_8") (pintype "bidirectional"))
    )
    (net (code "135") (name "unconnected-(U1-PB4-Pad10)") (class "Default")
      (node (ref "U1") (pin "10") (pinfunction "PB4_10") (pintype "bidirectional"))
    )
    (net (code "136") (name "unconnected-(U1-PB5-Pad11)") (class "Default")
      (node (ref "U1") (pin "11") (pinfunction "PB5_11") (pintype "bidirectional"))
    )
    (net (code "137") (name "unconnected-(U1-PB6-Pad12)") (class "Default")
      (node (ref "U1") (pin "12") (pinfunction "PB6_12") (pintype "bidirectional"))
    )
    (net (code "138") (name "unconnected-(U1-PB7-Pad13)") (class "Default")
      (node (ref "U1") (pin "13") (pinfunction "PB7_13") (pintype "bidirectional"))
    )
    (net (code "139") (name "unconnected-(U2-HOME-Pad2)") (class "Default")
      (node (ref "U2") (pin "2") (pinfunction "HOME_2") (pintype "bidirectional"))
    )
    (net (code "140") (name "unconnected-(U3-HOME-Pad2)") (class "Default")
      (node (ref "U3") (pin "2") (pinfunction "HOME_2") (pintype "bidirectional"))
    )
    (net (code "141") (name "unconnected-(U4-HOME-Pad2)") (class "Default")
      (node (ref "U4") (pin "2") (pinfunction "HOME_2") (pintype "bidirectional"))
    )
    (net (code "142") (name "unconnected-(U5-HOME-Pad2)") (class "Default")
      (node (ref "U5") (pin "2") (pinfunction "HOME_2") (pintype "bidirectional"))
    )
    (net (code "143") (name "unconnected-(U6-CBUS0-Pad15)") (class "Default")
      (node (ref "U6") (pin "15") (pinfunction "CBUS0_15") (pintype "bidirectional"))
    )
    (net (code "144") (name "unconnected-(U6-CBUS3-Pad16)") (class "Default")
      (node (ref "U6") (pin "16") (pinfunction "CBUS3_16") (pintype "bidirectional"))
    )
    (net (code "145") (name "unconnected-(U7-NC-Pad1)") (class "Default")
      (node (ref "U7") (pin "1") (pinfunction "NC_1") (pintype "no_connect"))
    )
    (net (code "146") (name "unconnected-(U7-NC-Pad2)") (class "Default")
      (node (ref "U7") (pin "2") (pinfunction "NC_2") (pintype "no_connect"))
    )
    (net (code "147") (name "unconnected-(U7-NC-Pad3)") (class "Default")
      (node (ref "U7") (pin "3") (pinfunction "NC_3") (pintype "no_connect"))
    )
    (net (code "148") (name "~{SS1}") (class "Default")
      (node (ref "J13") (pin "3") (pinfunction "3_3") (pintype "passive"))
      (node (ref "U1") (pin "20") (pinfunction "PC4_20") (pintype "bidirectional"))
    )
    (net (code "149") (name "~{SS2}") (class "Default")
      (node (ref "J13") (pin "2") (pinfunction "2_2") (pintype "passive"))
      (node (ref "U1") (pin "9") (pinfunction "PB3_9") (pintype "bidirectional"))
    )
  )
)
